# atmega2560_2.net
KiCad netlist of a schematic drawn in EAGLE
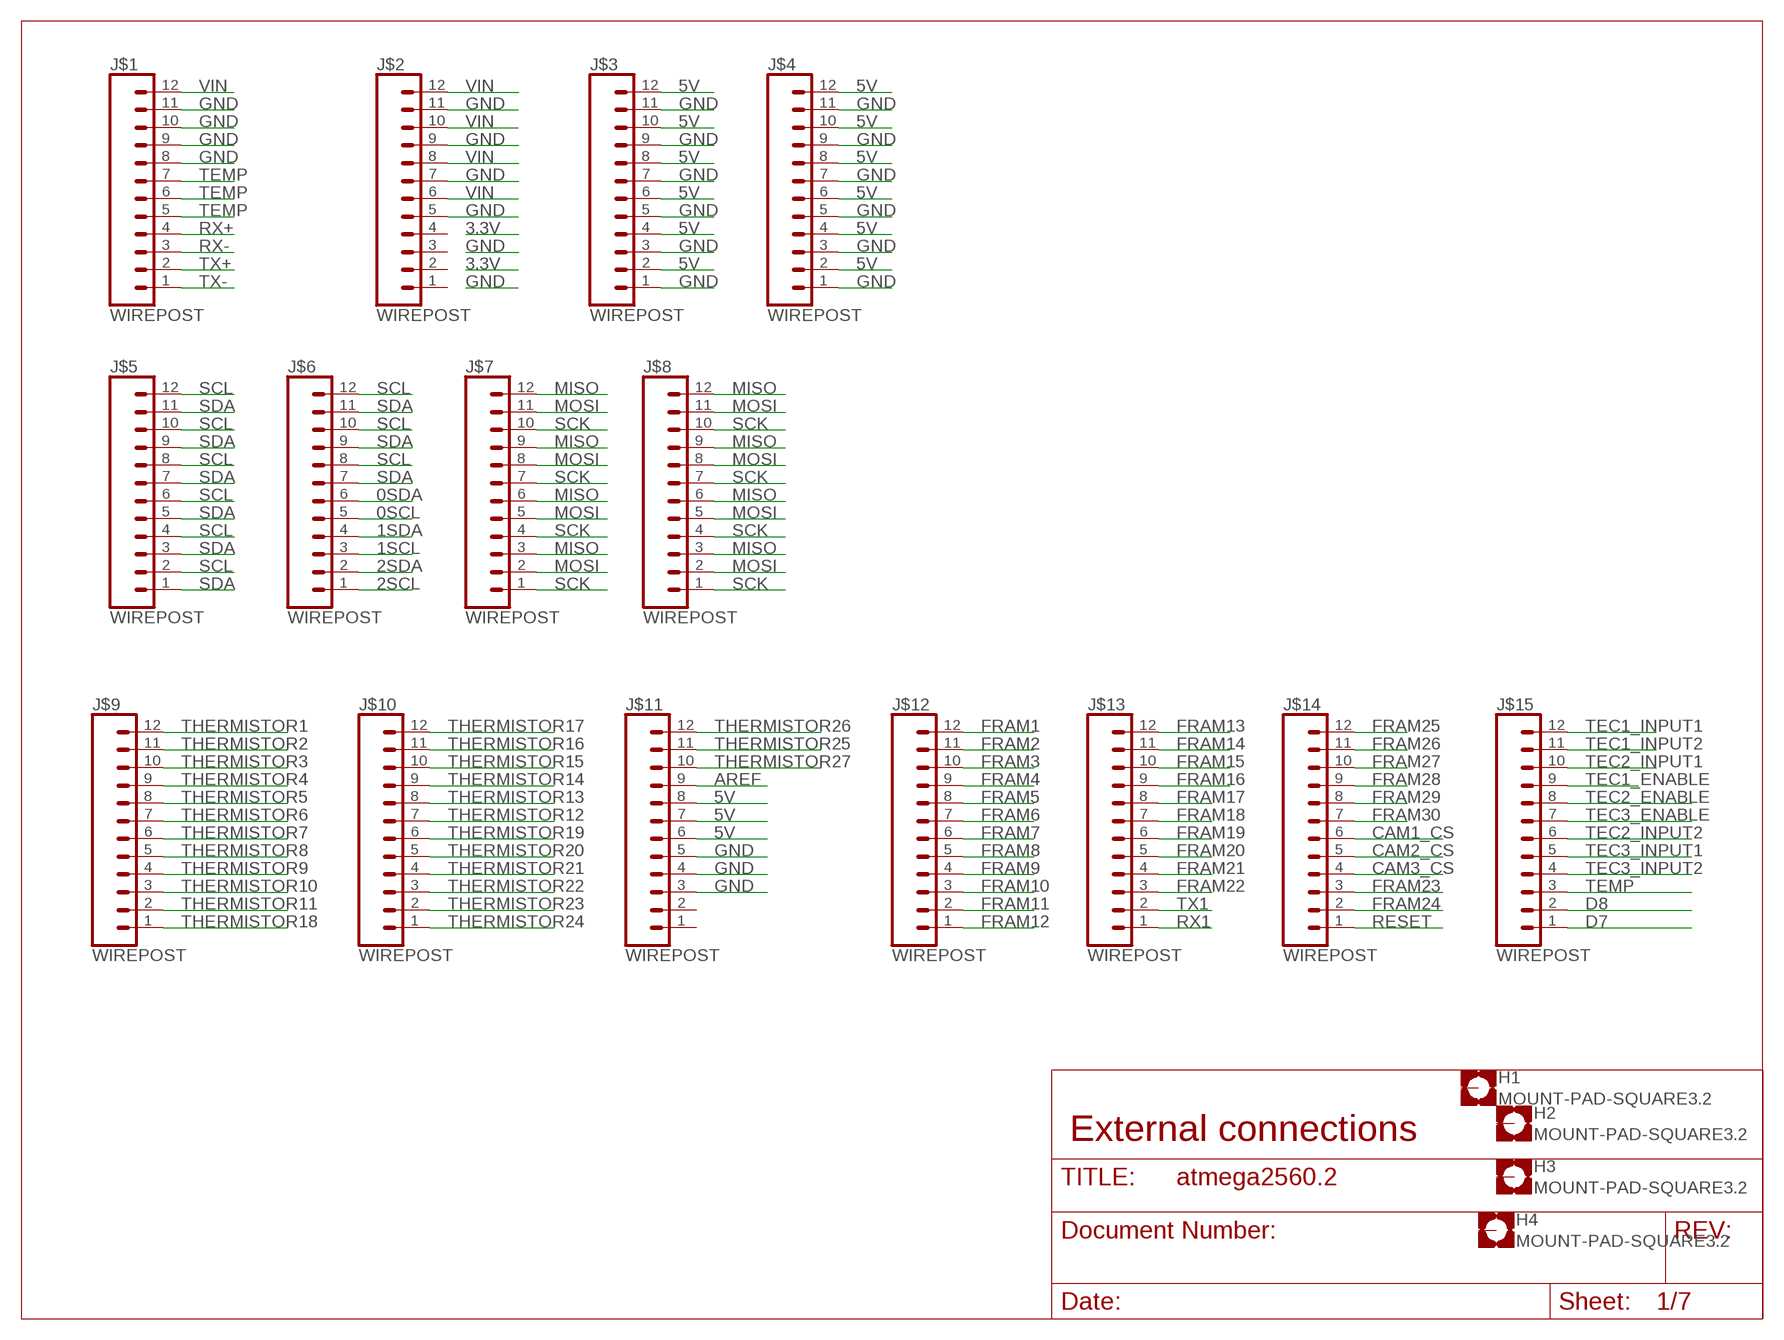
[diagram p0: schematic, sheet 1]
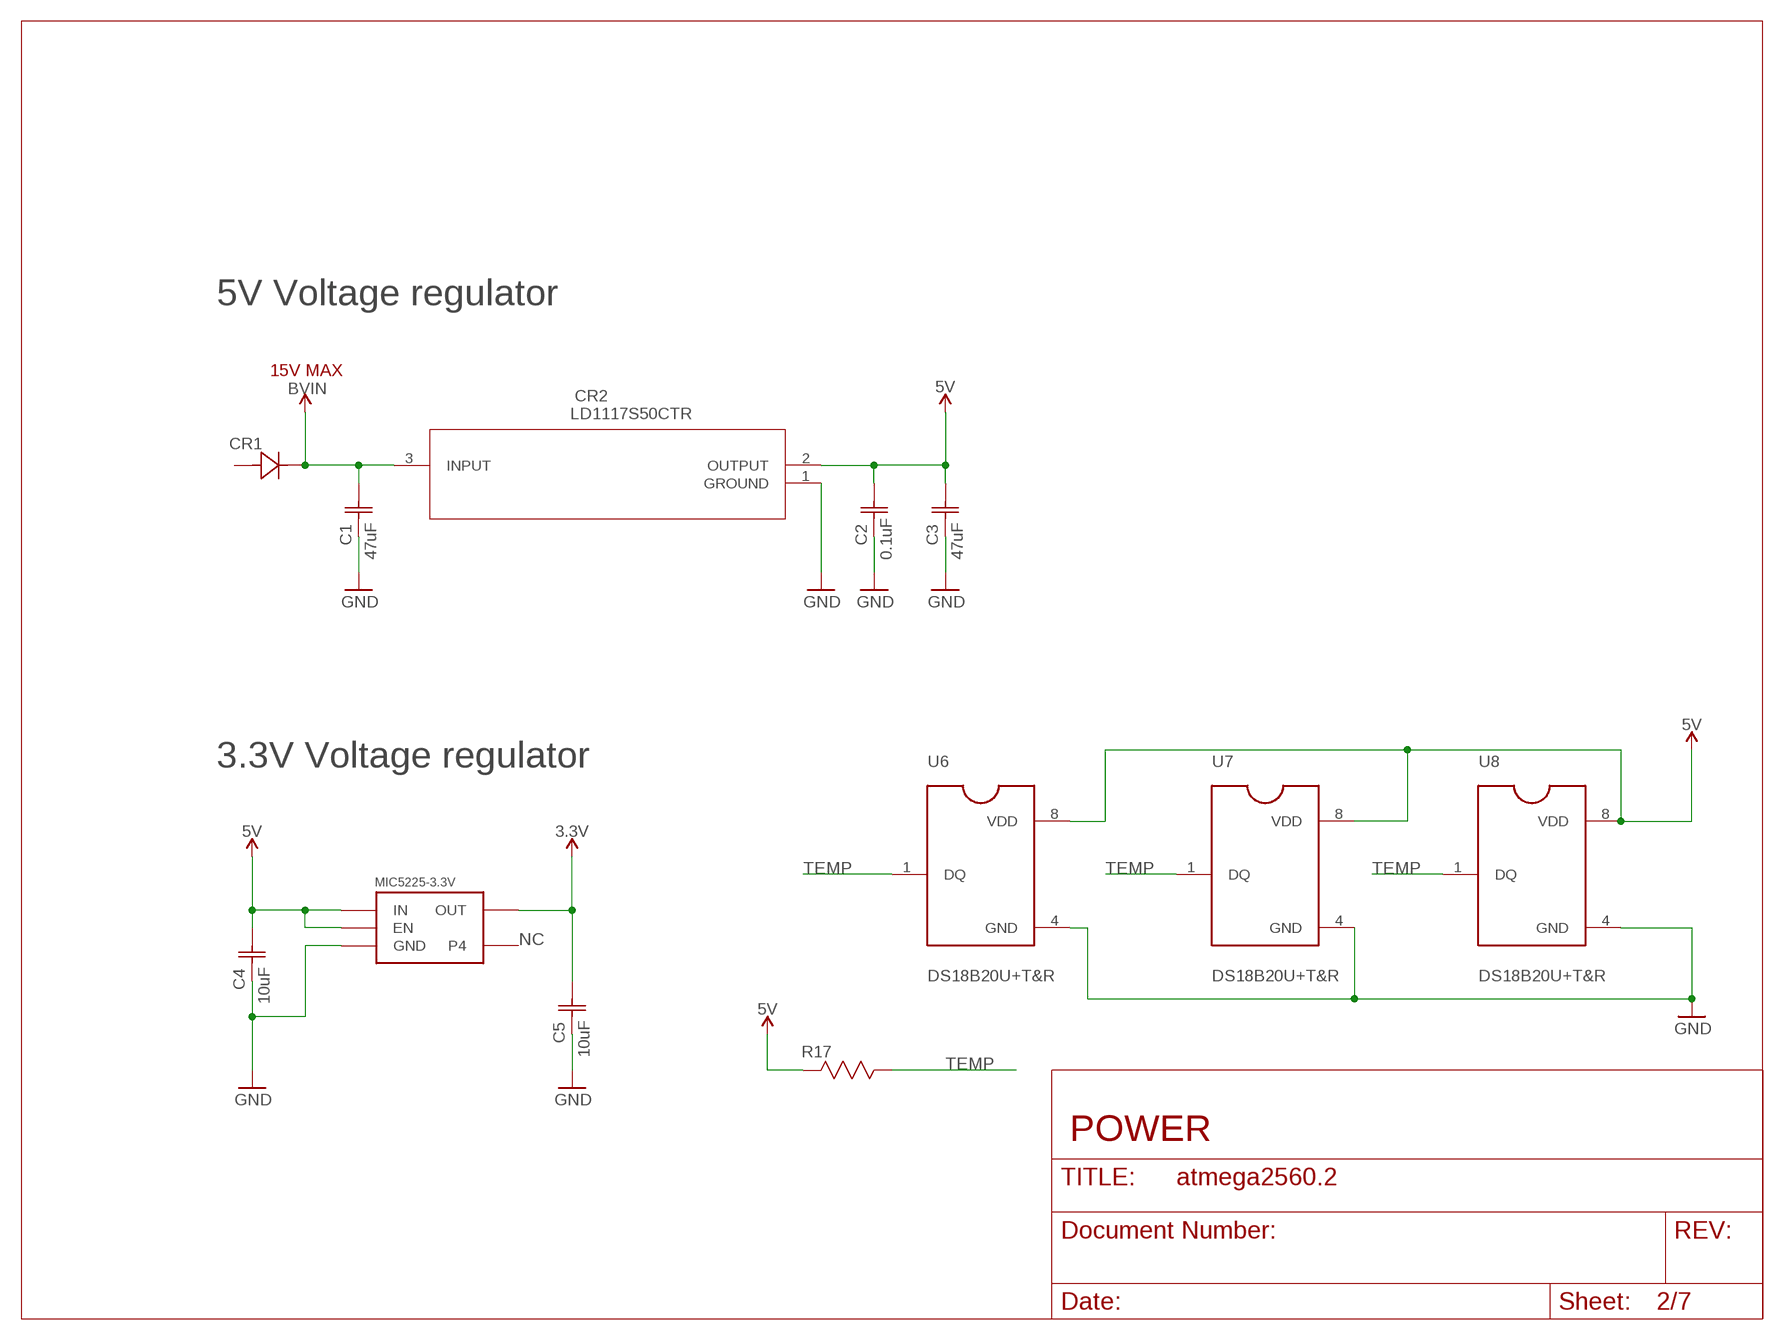
[diagram p1: schematic, sheet 2]
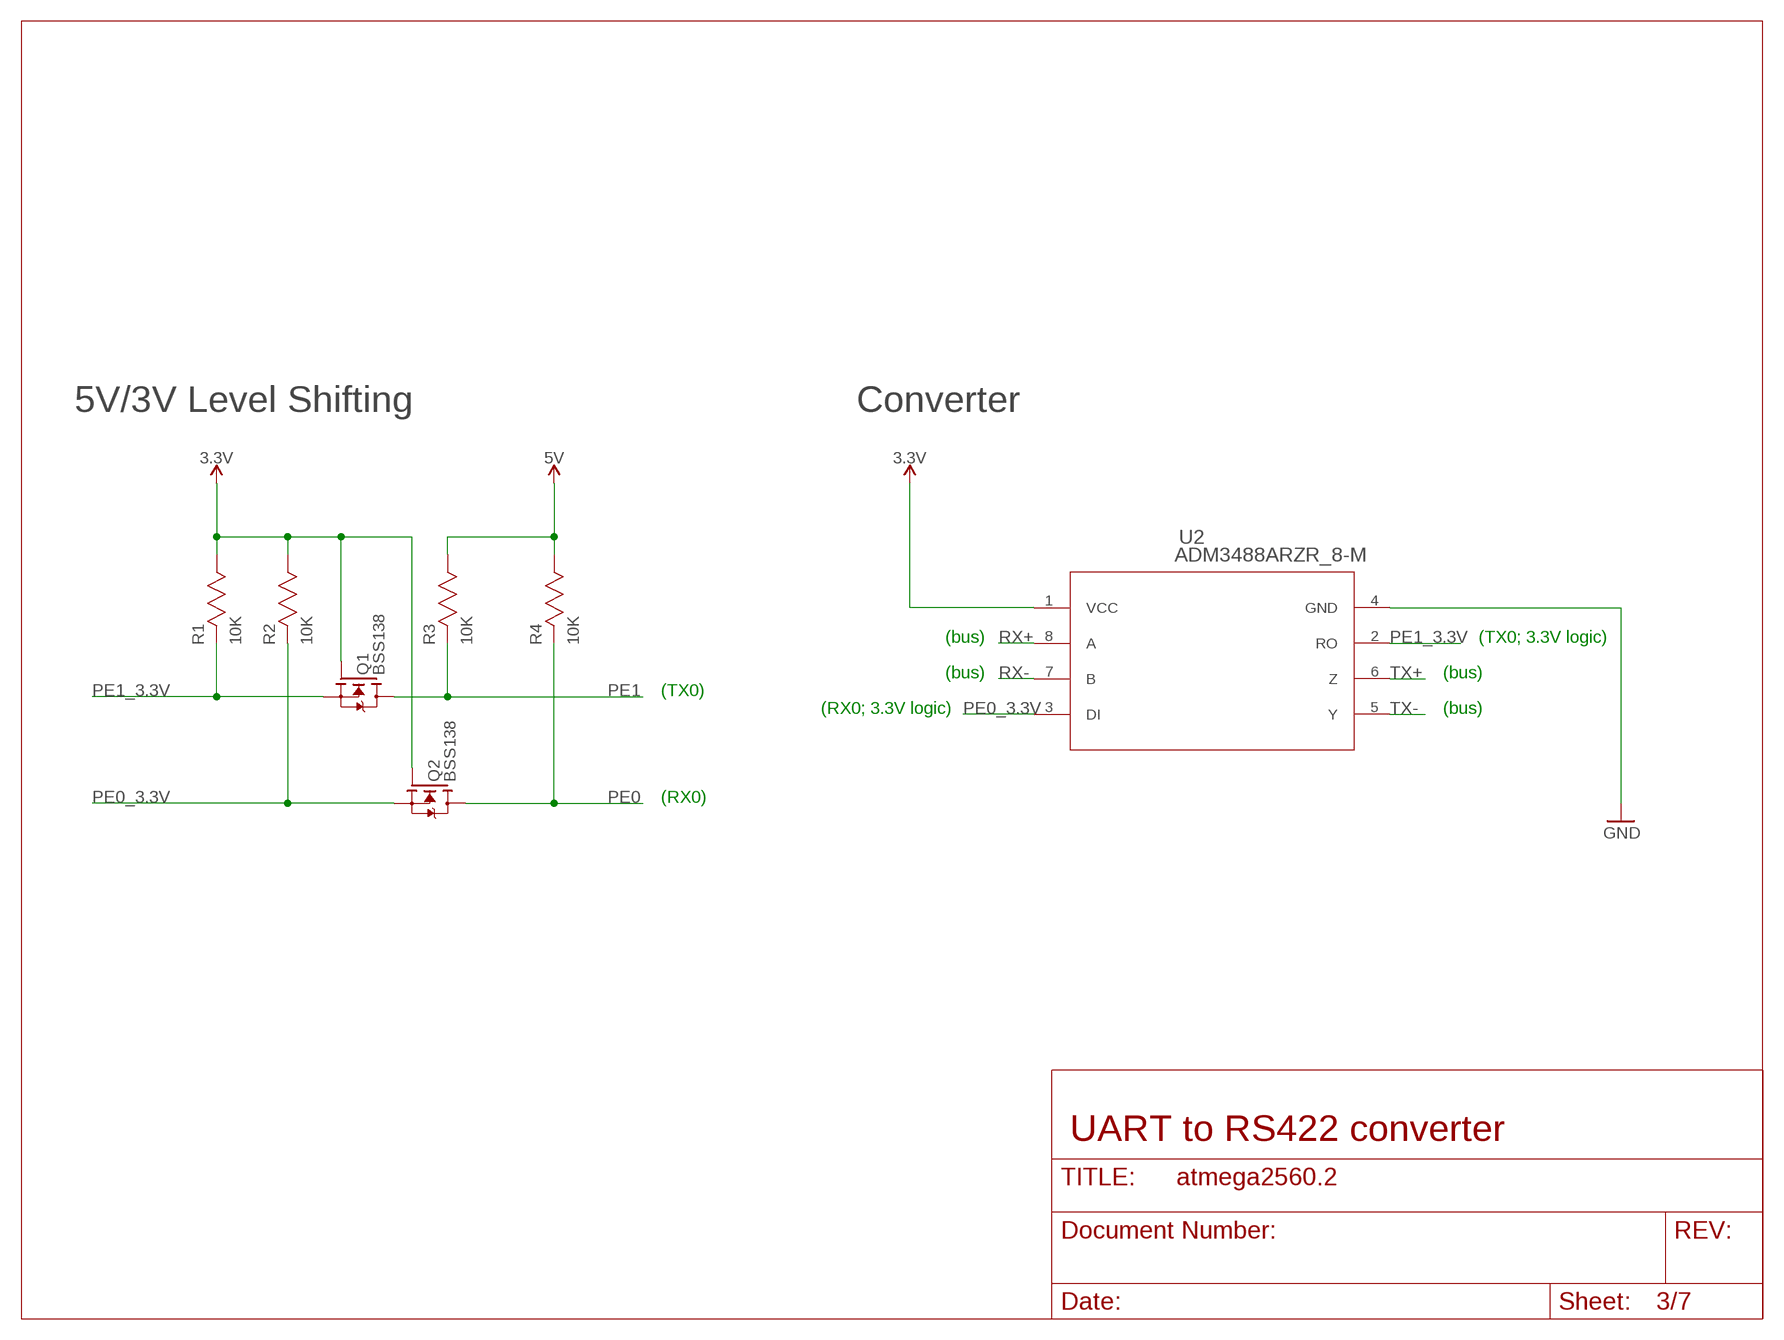
[diagram p2: schematic, sheet 3]
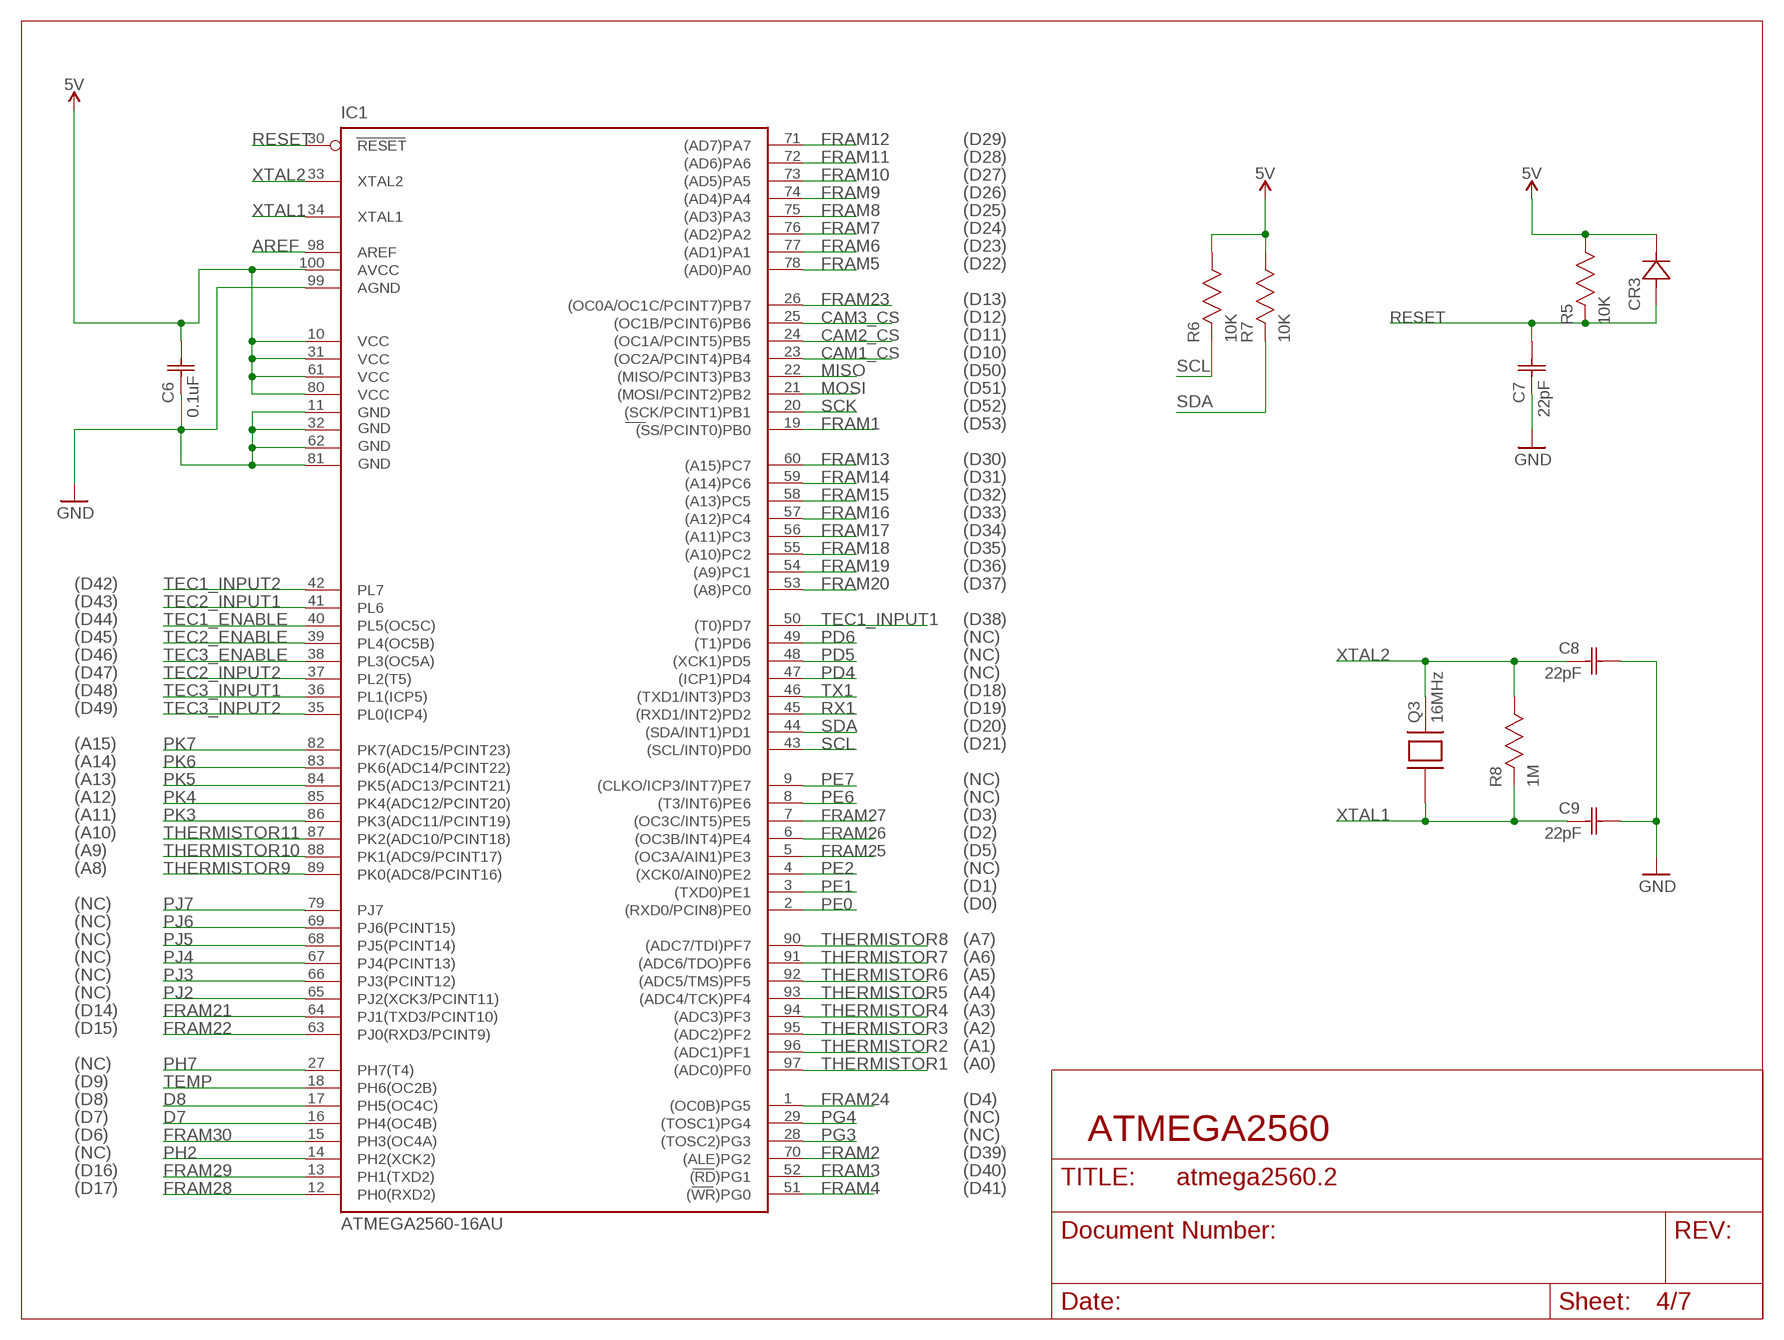
[diagram p3: schematic, sheet 4]
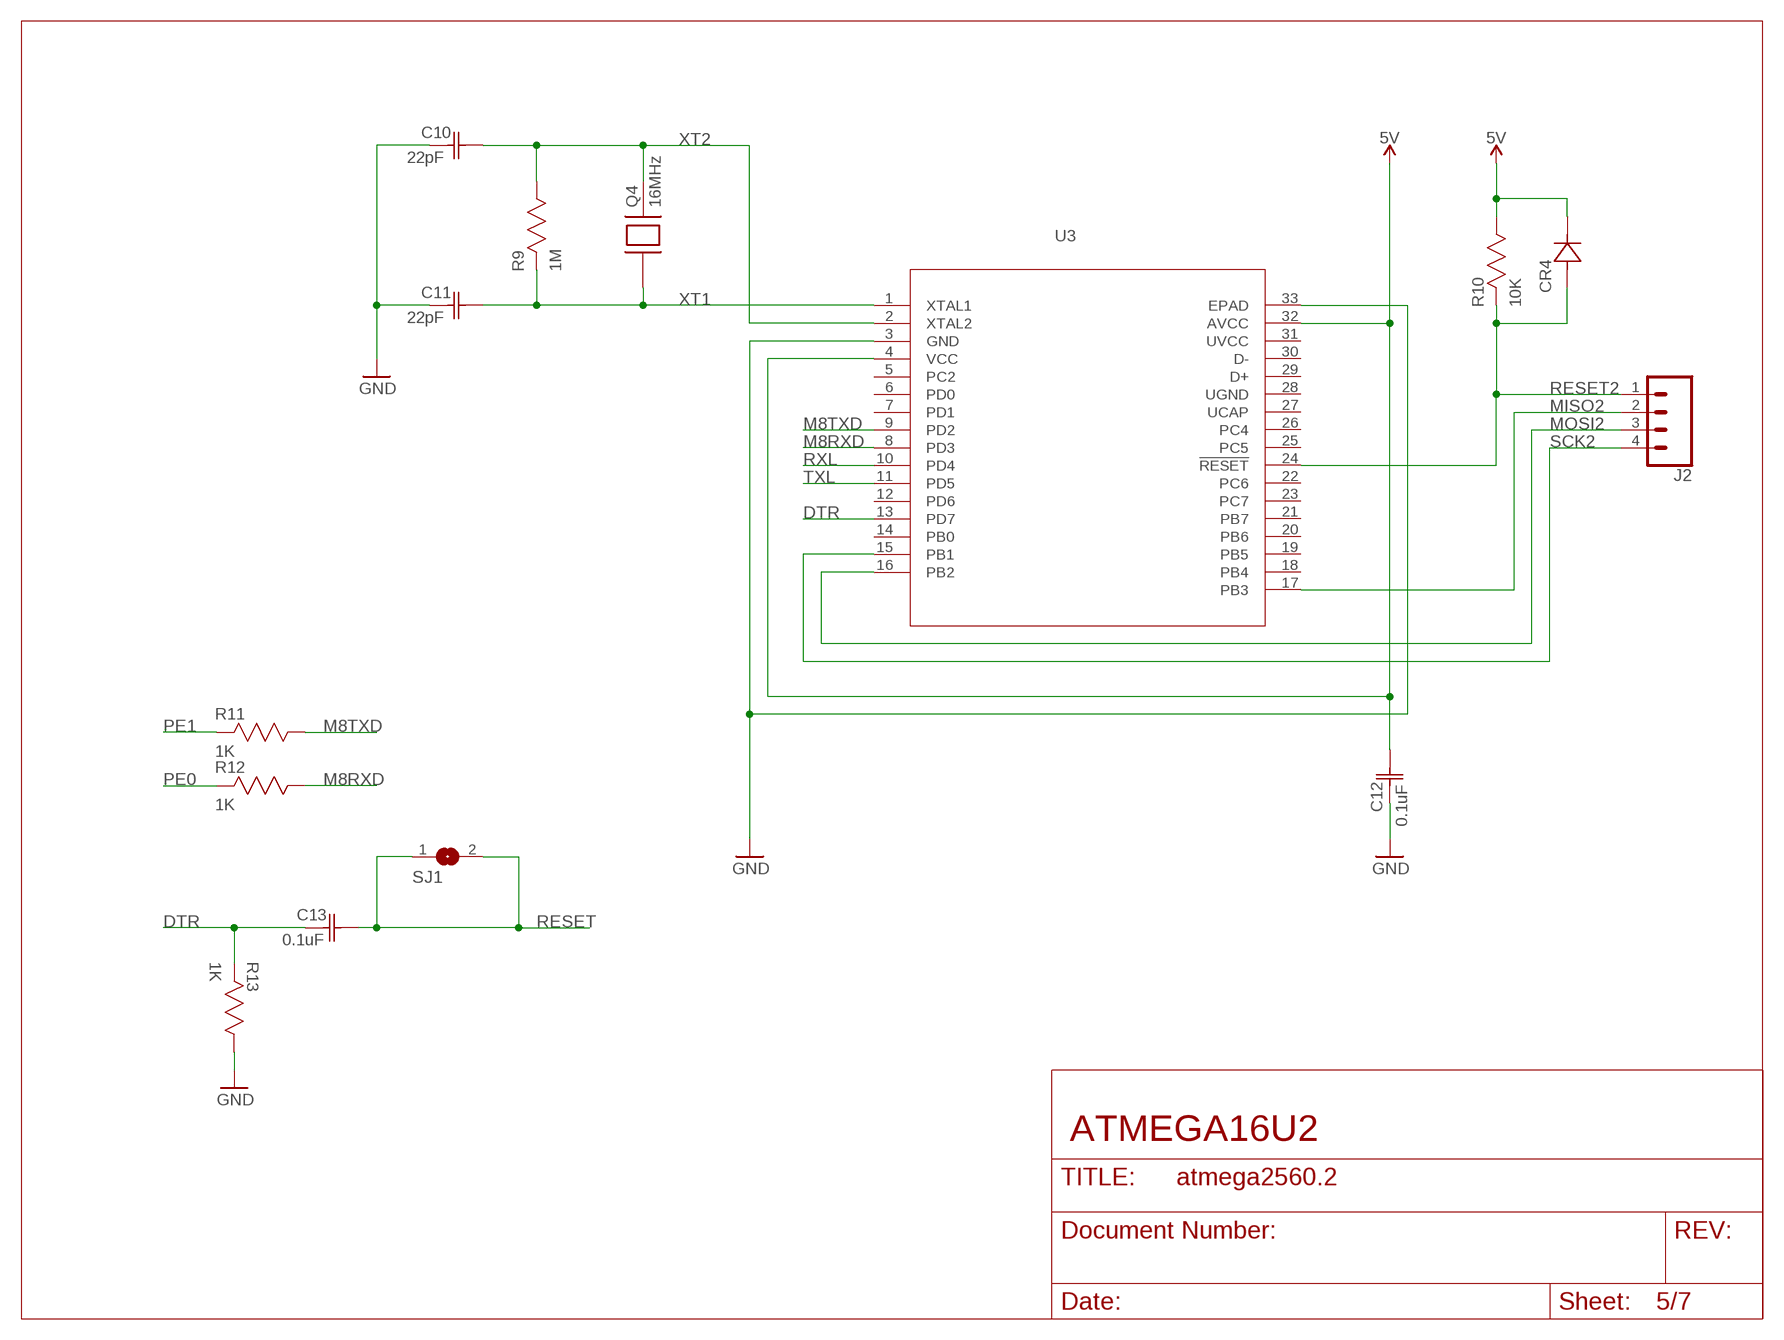
[diagram p4: schematic, sheet 5]
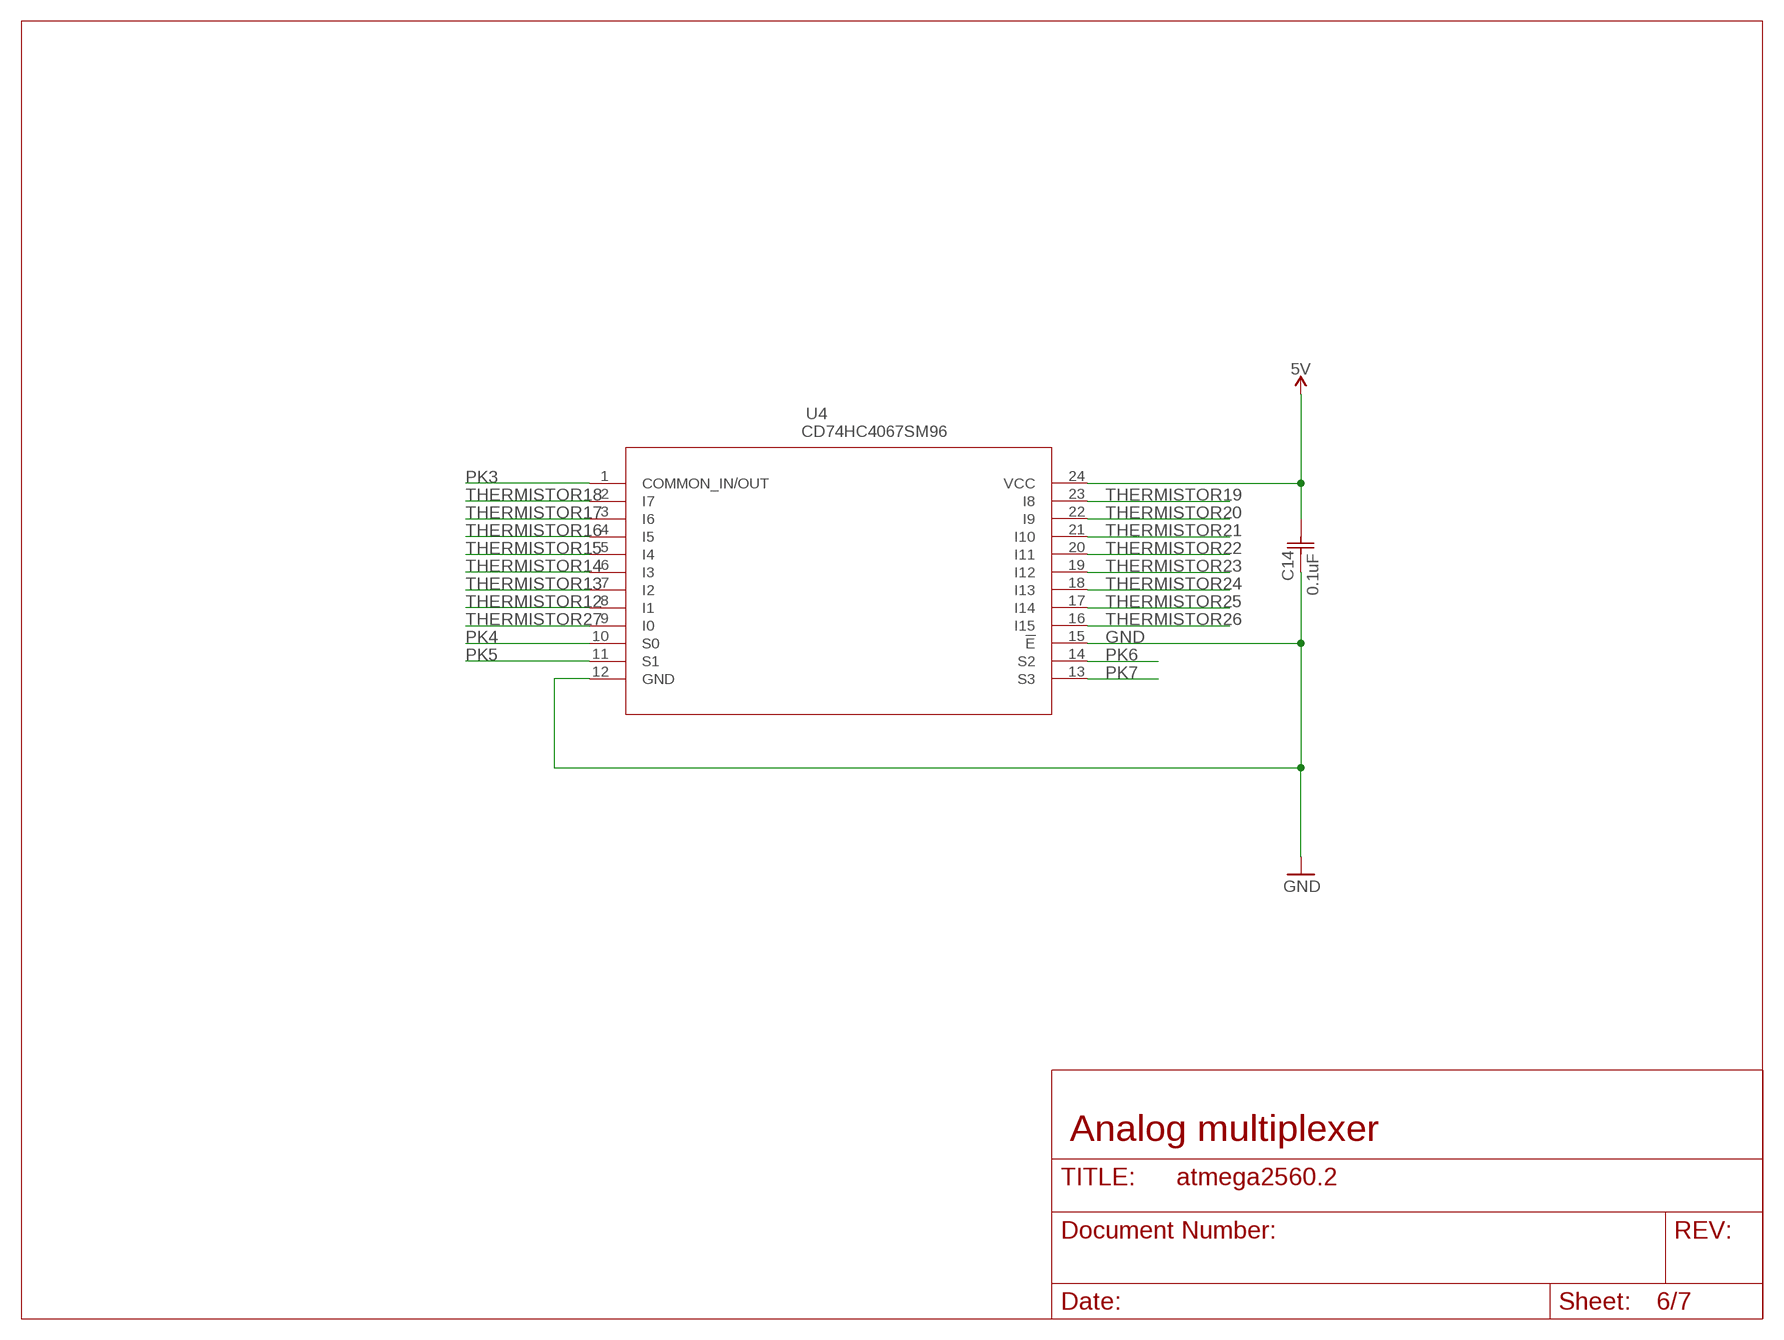
[diagram p5: schematic, sheet 6]
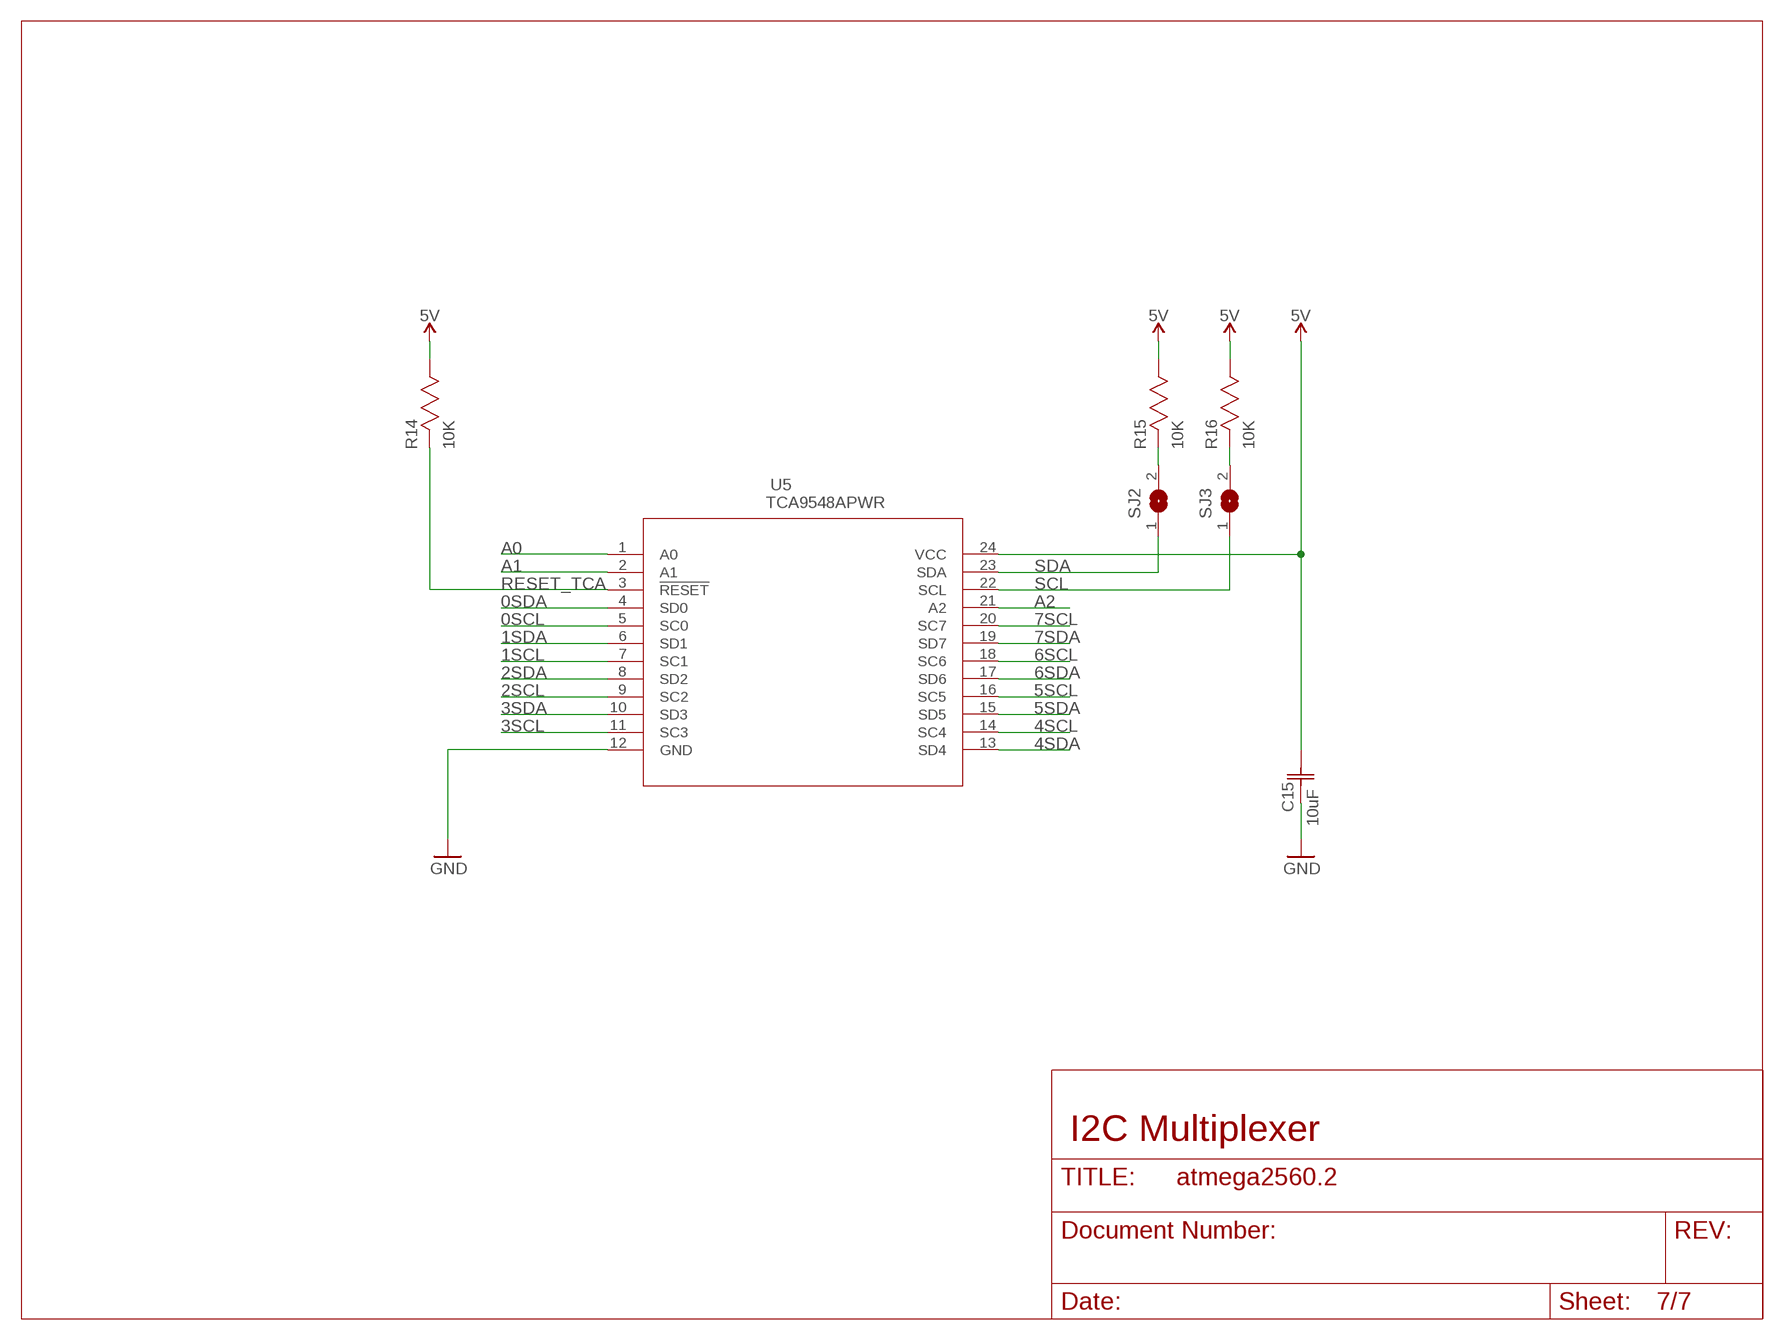
[diagram p6: schematic, sheet 7]

(export (version "E")
  (design (tool "Eeschema 10.0.6"))
  (components
    (comp (ref "C14")
      (value "0.1uF")
      (footprint "eagle-import:CAP_01")
      (fields (field (name "MANUFACTURER_PART_NUMBER") "CC0402KRX5R6BB104"))
      (libsource (lib "eagle-import") (part "CAP_01UF"))
    )
    (comp (ref "U4")
      (value "CD74HC4067SM96")
      (footprint "eagle-import:DB24")
      (libsource (lib "eagle-import") (part "CD74HC4067SM96"))
    )
    (comp (ref "Q1")
      (value "BSS138")
      (footprint "eagle-import:SOT-23")
      (fields (field (name "MANUFACTURER_PART_NUMBER") "BSS138TA"))
      (libsource (lib "eagle-import") (part "BSS138"))
    )
    (comp (ref "Q2")
      (value "BSS138")
      (footprint "eagle-import:SOT-23")
      (fields (field (name "MANUFACTURER_PART_NUMBER") "BSS138TA"))
      (libsource (lib "eagle-import") (part "BSS138"))
    )
    (comp (ref "R1")
      (value "10K")
      (footprint "eagle-import:RC0603N")
      (libsource (lib "eagle-import") (part "RES_10K"))
    )
    (comp (ref "R2")
      (value "10K")
      (footprint "eagle-import:RC0603N")
      (libsource (lib "eagle-import") (part "RES_10K"))
    )
    (comp (ref "R3")
      (value "10K")
      (footprint "eagle-import:RC0603N")
      (libsource (lib "eagle-import") (part "RES_10K"))
    )
    (comp (ref "R4")
      (value "10K")
      (footprint "eagle-import:RC0603N")
      (libsource (lib "eagle-import") (part "RES_10K"))
    )
    (comp (ref "U2")
      (value "ADM3488ARZR_8-M")
      (footprint "eagle-import:R_8-M")
      (fields (field (name "MANUFACTURER_PART_NUMBER") "ADM3488ARZ"))
      (libsource (lib "eagle-import") (part "ADM3488ARZR_8-M"))
    )
    (comp (ref "H1")
      (value "MOUNT-PAD-SQUARE3.2")
      (footprint "eagle-import:3,2-PAD-SQUARE")
      (libsource (lib "eagle-import") (part "MOUNT-PAD-SQUARE3.2"))
    )
    (comp (ref "H2")
      (value "MOUNT-PAD-SQUARE3.2")
      (footprint "eagle-import:3,2-PAD-SQUARE")
      (libsource (lib "eagle-import") (part "MOUNT-PAD-SQUARE3.2"))
    )
    (comp (ref "H3")
      (value "MOUNT-PAD-SQUARE3.2")
      (footprint "eagle-import:3,2-PAD-SQUARE")
      (libsource (lib "eagle-import") (part "MOUNT-PAD-SQUARE3.2"))
    )
    (comp (ref "H4")
      (value "MOUNT-PAD-SQUARE3.2")
      (footprint "eagle-import:3,2-PAD-SQUARE")
      (libsource (lib "eagle-import") (part "MOUNT-PAD-SQUARE3.2"))
    )
    (comp (ref "J$1")
      (value "WIREPOST")
      (footprint "eagle-import:WIREWRAPPOST")
      (libsource (lib "eagle-import") (part "WIREPOST"))
    )
    (comp (ref "J$2")
      (value "WIREPOST")
      (footprint "eagle-import:WIREWRAPPOST")
      (libsource (lib "eagle-import") (part "WIREPOST"))
    )
    (comp (ref "J$3")
      (value "WIREPOST")
      (footprint "eagle-import:WIREWRAPPOST")
      (libsource (lib "eagle-import") (part "WIREPOST"))
    )
    (comp (ref "J$4")
      (value "WIREPOST")
      (footprint "eagle-import:WIREWRAPPOST")
      (libsource (lib "eagle-import") (part "WIREPOST"))
    )
    (comp (ref "J$5")
      (value "WIREPOST")
      (footprint "eagle-import:WIREWRAPPOST")
      (libsource (lib "eagle-import") (part "WIREPOST"))
    )
    (comp (ref "J$6")
      (value "WIREPOST")
      (footprint "eagle-import:WIREWRAPPOST")
      (libsource (lib "eagle-import") (part "WIREPOST"))
    )
    (comp (ref "J$7")
      (value "WIREPOST")
      (footprint "eagle-import:WIREWRAPPOST")
      (libsource (lib "eagle-import") (part "WIREPOST"))
    )
    (comp (ref "J$8")
      (value "WIREPOST")
      (footprint "eagle-import:WIREWRAPPOST")
      (libsource (lib "eagle-import") (part "WIREPOST"))
    )
    (comp (ref "J$9")
      (value "WIREPOST")
      (footprint "eagle-import:WIREWRAPPOST")
      (libsource (lib "eagle-import") (part "WIREPOST"))
    )
    (comp (ref "J$10")
      (value "WIREPOST")
      (footprint "eagle-import:WIREWRAPPOST")
      (libsource (lib "eagle-import") (part "WIREPOST"))
    )
    (comp (ref "J$11")
      (value "WIREPOST")
      (footprint "eagle-import:WIREWRAPPOST")
      (libsource (lib "eagle-import") (part "WIREPOST"))
    )
    (comp (ref "J$12")
      (value "WIREPOST")
      (footprint "eagle-import:WIREWRAPPOST")
      (libsource (lib "eagle-import") (part "WIREPOST"))
    )
    (comp (ref "J$13")
      (value "WIREPOST")
      (footprint "eagle-import:WIREWRAPPOST")
      (libsource (lib "eagle-import") (part "WIREPOST"))
    )
    (comp (ref "J$14")
      (value "WIREPOST")
      (footprint "eagle-import:WIREWRAPPOST")
      (libsource (lib "eagle-import") (part "WIREPOST"))
    )
    (comp (ref "J$15")
      (value "WIREPOST")
      (footprint "eagle-import:WIREWRAPPOST")
      (libsource (lib "eagle-import") (part "WIREPOST"))
    )
    (comp (ref "C1")
      (value "47uF")
      (footprint "eagle-import:CAP_5750")
      (fields (field (name "MANUFACTURER_PART_NUMBER") "CGA9N3X7R1C476M230KB"))
      (libsource (lib "eagle-import") (part "CAP_47UF"))
    )
    (comp (ref "C2")
      (value "0.1uF")
      (footprint "eagle-import:CAP_01")
      (fields (field (name "MANUFACTURER_PART_NUMBER") "CC0402KRX5R6BB104"))
      (libsource (lib "eagle-import") (part "CAP_01UF"))
    )
    (comp (ref "C3")
      (value "47uF")
      (footprint "eagle-import:CAP_5750")
      (fields (field (name "MANUFACTURER_PART_NUMBER") "CGA9N3X7R1C476M230KB"))
      (libsource (lib "eagle-import") (part "CAP_47UF"))
    )
    (comp (ref "C4")
      (value "10uF")
      (footprint "eagle-import:CAP_GRM219R61A106KE44D")
      (libsource (lib "eagle-import") (part "CAP_10UF"))
    )
    (comp (ref "C5")
      (value "10uF")
      (footprint "eagle-import:CAP_GRM219R61A106KE44D")
      (libsource (lib "eagle-import") (part "CAP_10UF"))
    )
    (comp (ref "CR1")
      (value "DIODE_600V_3A")
      (footprint "eagle-import:DIODE_600V_3A")
      (fields (field (name "MANUFACTURER_PART_NUMBER") "RS3JB13F"))
      (libsource (lib "eagle-import") (part "DIODE_600V_3A"))
    )
    (comp (ref "CR2")
      (value "LD1117S50CTR")
      (footprint "eagle-import:SOT-223")
      (libsource (lib "eagle-import") (part "LD1117S50CTR"))
    )
    (comp (ref "R17")
      (value "RES_4_7K")
      (footprint "eagle-import:RC0603N")
      (libsource (lib "eagle-import") (part "RES_4_7K"))
    )
    (comp (ref "U1")
      (value "MIC5225")
      (footprint "eagle-import:SOT23-5")
      (libsource (lib "eagle-import") (part "MIC5225"))
    )
    (comp (ref "U6")
      (value "DS18B20U+T&R")
      (footprint "eagle-import:SOP65P500X110-8N")
      (fields (field (name "MF") "Maxim Integrated") (field (name "MP") "DS18B20U+T&amp;R"))
      (libsource (lib "eagle-import") (part "DS18B20U+T&R"))
    )
    (comp (ref "U7")
      (value "DS18B20U+T&R")
      (footprint "eagle-import:SOP65P500X110-8N")
      (fields (field (name "MF") "Maxim Integrated") (field (name "MP") "DS18B20U+T&amp;R"))
      (libsource (lib "eagle-import") (part "DS18B20U+T&R"))
    )
    (comp (ref "U8")
      (value "DS18B20U+T&R")
      (footprint "eagle-import:SOP65P500X110-8N")
      (fields (field (name "MF") "Maxim Integrated") (field (name "MP") "DS18B20U+T&amp;R"))
      (libsource (lib "eagle-import") (part "DS18B20U+T&R"))
    )
    (comp (ref "C15")
      (value "10uF")
      (footprint "eagle-import:CAP_GRM219R61A106KE44D")
      (libsource (lib "eagle-import") (part "CAP_10UF"))
    )
    (comp (ref "R14")
      (value "10K")
      (footprint "eagle-import:RC0603N")
      (libsource (lib "eagle-import") (part "RES_10K"))
    )
    (comp (ref "R15")
      (value "10K")
      (footprint "eagle-import:RC0603N")
      (libsource (lib "eagle-import") (part "RES_10K"))
    )
    (comp (ref "R16")
      (value "10K")
      (footprint "eagle-import:RC0603N")
      (libsource (lib "eagle-import") (part "RES_10K"))
    )
    (comp (ref "SJ2")
      (value "SOLDERJUMPERCLOSED")
      (footprint "eagle-import:SOLDERJUMPER_CLOSEDWIRE")
      (libsource (lib "eagle-import") (part "SOLDERJUMPERCLOSED"))
    )
    (comp (ref "SJ3")
      (value "SOLDERJUMPERCLOSED")
      (footprint "eagle-import:SOLDERJUMPER_CLOSEDWIRE")
      (libsource (lib "eagle-import") (part "SOLDERJUMPERCLOSED"))
    )
    (comp (ref "U5")
      (value "TCA9548APWR")
      (footprint "eagle-import:PW24")
      (libsource (lib "eagle-import") (part "TCA9548APWR"))
    )
    (comp (ref "C10")
      (value "22pF")
      (footprint "eagle-import:CC0805N")
      (libsource (lib "eagle-import") (part "CAP_22PF"))
    )
    (comp (ref "C11")
      (value "22pF")
      (footprint "eagle-import:CC0805N")
      (libsource (lib "eagle-import") (part "CAP_22PF"))
    )
    (comp (ref "C12")
      (value "0.1uF")
      (footprint "eagle-import:CAP_01")
      (fields (field (name "MANUFACTURER_PART_NUMBER") "CC0402KRX5R6BB104"))
      (libsource (lib "eagle-import") (part "CAP_01UF"))
    )
    (comp (ref "C13")
      (value "0.1uF")
      (footprint "eagle-import:CAP_01")
      (fields (field (name "MANUFACTURER_PART_NUMBER") "CC0402KRX5R6BB104"))
      (libsource (lib "eagle-import") (part "CAP_01UF"))
    )
    (comp (ref "CR4")
      (value "DIODE_600V_3A")
      (footprint "eagle-import:DIODE_600V_3A")
      (fields (field (name "MANUFACTURER_PART_NUMBER") "RS3JB13F"))
      (libsource (lib "eagle-import") (part "DIODE_600V_3A"))
    )
    (comp (ref "J2")
      (value "CONN_04")
      (footprint "eagle-import:1X04")
      (libsource (lib "eagle-import") (part "CONN_04"))
    )
    (comp (ref "Q4")
      (value "16MHz")
      (footprint "eagle-import:OSCILLATOR")
      (libsource (lib "eagle-import") (part "OSILLATOR"))
    )
    (comp (ref "R9")
      (value "1M")
      (footprint "eagle-import:RC0603N")
      (libsource (lib "eagle-import") (part "RES_1M"))
    )
    (comp (ref "R10")
      (value "10K")
      (footprint "eagle-import:RC0603N")
      (libsource (lib "eagle-import") (part "RES_10K"))
    )
    (comp (ref "R11")
      (value "1K")
      (footprint "eagle-import:RC0603N")
      (libsource (lib "eagle-import") (part "RES_1K"))
    )
    (comp (ref "R12")
      (value "1K")
      (footprint "eagle-import:RC0603N")
      (libsource (lib "eagle-import") (part "RES_1K"))
    )
    (comp (ref "R13")
      (value "1K")
      (footprint "eagle-import:RC0603N")
      (libsource (lib "eagle-import") (part "RES_1K"))
    )
    (comp (ref "SJ1") (value "SJ") (footprint "eagle-import:SJ") (libsource (lib "eagle-import") (part "SJ")))
    (comp (ref "U3")
      (value "ATMEGA16U2-MU")
      (footprint "eagle-import:32M1-A")
      (fields (field (name "MANUFACTURER_PART_NUMBER") "ATMEGA16U2MU"))
      (libsource (lib "eagle-import") (part "ATMEGA16U2-MU"))
    )
    (comp (ref "C6")
      (value "0.1uF")
      (footprint "eagle-import:CAP_01")
      (fields (field (name "MANUFACTURER_PART_NUMBER") "CC0402KRX5R6BB104"))
      (libsource (lib "eagle-import") (part "CAP_01UF"))
    )
    (comp (ref "C7")
      (value "22pF")
      (footprint "eagle-import:CC0805N")
      (libsource (lib "eagle-import") (part "CAP_22PF"))
    )
    (comp (ref "C8")
      (value "22pF")
      (footprint "eagle-import:CC0805N")
      (libsource (lib "eagle-import") (part "CAP_22PF"))
    )
    (comp (ref "C9")
      (value "22pF")
      (footprint "eagle-import:CC0805N")
      (libsource (lib "eagle-import") (part "CAP_22PF"))
    )
    (comp (ref "CR3")
      (value "DIODE_600V_3A")
      (footprint "eagle-import:DIODE_600V_3A")
      (fields (field (name "MANUFACTURER_PART_NUMBER") "RS3JB13F"))
      (libsource (lib "eagle-import") (part "DIODE_600V_3A"))
    )
    (comp (ref "IC1")
      (value "ATMEGA2560-16AU")
      (footprint "eagle-import:TQFP100")
      (libsource (lib "eagle-import") (part "ATMEGA2560AU2560-16"))
    )
    (comp (ref "Q3")
      (value "16MHz")
      (footprint "eagle-import:OSCILLATOR")
      (libsource (lib "eagle-import") (part "OSILLATOR"))
    )
    (comp (ref "R5")
      (value "10K")
      (footprint "eagle-import:RC0603N")
      (libsource (lib "eagle-import") (part "RES_10K"))
    )
    (comp (ref "R6")
      (value "10K")
      (footprint "eagle-import:RC0603N")
      (libsource (lib "eagle-import") (part "RES_10K"))
    )
    (comp (ref "R7")
      (value "10K")
      (footprint "eagle-import:RC0603N")
      (libsource (lib "eagle-import") (part "RES_10K"))
    )
    (comp (ref "R8")
      (value "1M")
      (footprint "eagle-import:RC0603N")
      (libsource (lib "eagle-import") (part "RES_1M"))
    )
  )
  (nets
    (net (code "1") (name "0SCL") (class "Default")
      (node (ref "J$6") (pin "5") (pinfunction "5_5") (pintype "passive"))
      (node (ref "U5") (pin "5") (pinfunction "SC0_5") (pintype "passive"))
    )
    (net (code "2") (name "0SDA") (class "Default")
      (node (ref "J$6") (pin "6") (pinfunction "6_6") (pintype "passive"))
      (node (ref "U5") (pin "4") (pinfunction "SD0_4") (pintype "passive"))
    )
    (net (code "3") (name "1SCL") (class "Default")
      (node (ref "J$6") (pin "3") (pinfunction "3_3") (pintype "passive"))
      (node (ref "U5") (pin "7") (pinfunction "SC1_7") (pintype "passive"))
    )
    (net (code "4") (name "1SDA") (class "Default")
      (node (ref "J$6") (pin "4") (pinfunction "4_4") (pintype "passive"))
      (node (ref "U5") (pin "6") (pinfunction "SD1_6") (pintype "passive"))
    )
    (net (code "5") (name "2SCL") (class "Default")
      (node (ref "J$6") (pin "1") (pinfunction "1_1") (pintype "passive"))
      (node (ref "U5") (pin "9") (pinfunction "SC2_9") (pintype "passive"))
    )
    (net (code "6") (name "2SDA") (class "Default")
      (node (ref "J$6") (pin "2") (pinfunction "2_2") (pintype "passive"))
      (node (ref "U5") (pin "8") (pinfunction "SD2_8") (pintype "passive"))
    )
    (net (code "7") (name "3.3V") (class "Default")
      (node (ref "C5") (pin "2") (pinfunction "2_2") (pintype "passive"))
      (node (ref "Q1") (pin "G") (pinfunction "G_G") (pintype "passive"))
      (node (ref "Q2") (pin "G") (pinfunction "G_G") (pintype "passive"))
      (node (ref "R1") (pin "1") (pinfunction "11_1") (pintype "passive"))
      (node (ref "R2") (pin "1") (pinfunction "11_1") (pintype "passive"))
      (node (ref "U1") (pin "OUT") (pinfunction "OUT_OUT") (pintype "bidirectional"))
      (node (ref "U2") (pin "1") (pinfunction "VCC_1") (pintype "passive"))
    )
    (net (code "8") (name "3SCL") (class "Default")
      (node (ref "U5") (pin "11") (pinfunction "SC3_11") (pintype "passive"))
    )
    (net (code "9") (name "3SDA") (class "Default")
      (node (ref "U5") (pin "10") (pinfunction "SD3_10") (pintype "passive"))
    )
    (net (code "10") (name "4SCL") (class "Default")
      (node (ref "U5") (pin "14") (pinfunction "SC4_14") (pintype "passive"))
    )
    (net (code "11") (name "4SDA") (class "Default")
      (node (ref "U5") (pin "13") (pinfunction "SD4_13") (pintype "passive"))
    )
    (net (code "12") (name "5SCL") (class "Default")
      (node (ref "U5") (pin "16") (pinfunction "SC5_16") (pintype "passive"))
    )
    (net (code "13") (name "5SDA") (class "Default")
      (node (ref "U5") (pin "15") (pinfunction "SD5_15") (pintype "passive"))
    )
    (net (code "14") (name "5V") (class "Default")
      (node (ref "C12") (pin "2") (pinfunction "2_2") (pintype "passive"))
      (node (ref "C14") (pin "2") (pinfunction "2_2") (pintype "passive"))
      (node (ref "C15") (pin "2") (pinfunction "2_2") (pintype "passive"))
      (node (ref "C2") (pin "2") (pinfunction "2_2") (pintype "passive"))
      (node (ref "C3") (pin "2") (pinfunction "2_2") (pintype "passive"))
      (node (ref "C4") (pin "2") (pinfunction "2_2") (pintype "passive"))
      (node (ref "C6") (pin "2") (pinfunction "2_2") (pintype "passive"))
      (node (ref "CR2") (pin "2") (pinfunction "OUTPUT_2") (pintype "passive"))
      (node (ref "CR3") (pin "1") (pinfunction "12_1") (pintype "passive"))
      (node (ref "CR4") (pin "1") (pinfunction "12_1") (pintype "passive"))
      (node (ref "IC1") (pin "10") (pinfunction "VCC_10") (pintype "power_in"))
      (node (ref "IC1") (pin "100") (pinfunction "AVCC_100") (pintype "power_in"))
      (node (ref "IC1") (pin "31") (pinfunction "VCC1_31") (pintype "power_in"))
      (node (ref "IC1") (pin "61") (pinfunction "VCC2_61") (pintype "power_in"))
      (node (ref "IC1") (pin "80") (pinfunction "VCC3_80") (pintype "power_in"))
      (node (ref "J$11") (pin "6") (pinfunction "6_6") (pintype "passive"))
      (node (ref "J$11") (pin "7") (pinfunction "7_7") (pintype "passive"))
      (node (ref "J$11") (pin "8") (pinfunction "8_8") (pintype "passive"))
      (node (ref "J$3") (pin "10") (pinfunction "10_10") (pintype "passive"))
      (node (ref "J$3") (pin "12") (pinfunction "12_12") (pintype "passive"))
      (node (ref "J$3") (pin "2") (pinfunction "2_2") (pintype "passive"))
      (node (ref "J$3") (pin "4") (pinfunction "4_4") (pintype "passive"))
      (node (ref "J$3") (pin "6") (pinfunction "6_6") (pintype "passive"))
      (node (ref "J$3") (pin "8") (pinfunction "8_8") (pintype "passive"))
      (node (ref "J$4") (pin "10") (pinfunction "10_10") (pintype "passive"))
      (node (ref "J$4") (pin "12") (pinfunction "12_12") (pintype "passive"))
      (node (ref "J$4") (pin "2") (pinfunction "2_2") (pintype "passive"))
      (node (ref "J$4") (pin "4") (pinfunction "4_4") (pintype "passive"))
      (node (ref "J$4") (pin "6") (pinfunction "6_6") (pintype "passive"))
      (node (ref "J$4") (pin "8") (pinfunction "8_8") (pintype "passive"))
      (node (ref "R10") (pin "1") (pinfunction "11_1") (pintype "passive"))
      (node (ref "R14") (pin "1") (pinfunction "11_1") (pintype "passive"))
      (node (ref "R15") (pin "1") (pinfunction "11_1") (pintype "passive"))
      (node (ref "R16") (pin "1") (pinfunction "11_1") (pintype "passive"))
      (node (ref "R17") (pin "2") (pinfunction "22_2") (pintype "passive"))
      (node (ref "R3") (pin "1") (pinfunction "11_1") (pintype "passive"))
      (node (ref "R4") (pin "1") (pinfunction "11_1") (pintype "passive"))
      (node (ref "R5") (pin "1") (pinfunction "11_1") (pintype "passive"))
      (node (ref "R6") (pin "1") (pinfunction "11_1") (pintype "passive"))
      (node (ref "R7") (pin "1") (pinfunction "11_1") (pintype "passive"))
      (node (ref "U1") (pin "EN") (pinfunction "EN_EN") (pintype "bidirectional"))
      (node (ref "U1") (pin "IN") (pinfunction "IN_IN") (pintype "bidirectional"))
      (node (ref "U3") (pin "32") (pinfunction "AVCC_32") (pintype "power_in"))
      (node (ref "U3") (pin "4") (pinfunction "VCC_4") (pintype "power_in"))
      (node (ref "U4") (pin "24") (pinfunction "VCC_24") (pintype "power_in"))
      (node (ref "U5") (pin "24") (pinfunction "VCC_24") (pintype "power_in"))
      (node (ref "U6") (pin "8") (pinfunction "VDD_8") (pintype "power_in"))
      (node (ref "U7") (pin "8") (pinfunction "VDD_8") (pintype "power_in"))
      (node (ref "U8") (pin "8") (pinfunction "VDD_8") (pintype "power_in"))
    )
    (net (code "15") (name "6SCL") (class "Default")
      (node (ref "U5") (pin "18") (pinfunction "SC6_18") (pintype "passive"))
    )
    (net (code "16") (name "6SDA") (class "Default")
      (node (ref "U5") (pin "17") (pinfunction "SD6_17") (pintype "passive"))
    )
    (net (code "17") (name "7SCL") (class "Default")
      (node (ref "U5") (pin "20") (pinfunction "SC7_20") (pintype "passive"))
    )
    (net (code "18") (name "7SDA") (class "Default")
      (node (ref "U5") (pin "19") (pinfunction "SD7_19") (pintype "passive"))
    )
    (net (code "19") (name "A0") (class "Default")
      (node (ref "U5") (pin "1") (pinfunction "A0_1") (pintype "input"))
    )
    (net (code "20") (name "A1") (class "Default")
      (node (ref "U5") (pin "2") (pinfunction "A1_2") (pintype "input"))
    )
    (net (code "21") (name "A2") (class "Default")
      (node (ref "U5") (pin "21") (pinfunction "A2_21") (pintype "input"))
    )
    (net (code "22") (name "AREF") (class "Default")
      (node (ref "IC1") (pin "98") (pinfunction "AREF_98") (pintype "bidirectional"))
      (node (ref "J$11") (pin "9") (pinfunction "9_9") (pintype "passive"))
    )
    (net (code "23") (name "CAM1_CS") (class "Default")
      (node (ref "IC1") (pin "23") (pinfunction "(OC2A/PCINT4)PB4_23") (pintype "bidirectional"))
      (node (ref "J$14") (pin "6") (pinfunction "6_6") (pintype "passive"))
    )
    (net (code "24") (name "CAM2_CS") (class "Default")
      (node (ref "IC1") (pin "24") (pinfunction "(OC1A/PCINT5)PB5_24") (pintype "bidirectional"))
      (node (ref "J$14") (pin "5") (pinfunction "5_5") (pintype "passive"))
    )
    (net (code "25") (name "CAM3_CS") (class "Default")
      (node (ref "IC1") (pin "25") (pinfunction "(OC1B/PCINT6)PB6_25") (pintype "bidirectional"))
      (node (ref "J$14") (pin "4") (pinfunction "4_4") (pintype "passive"))
    )
    (net (code "26") (name "D7") (class "Default")
      (node (ref "IC1") (pin "16") (pinfunction "PH4(OC4B)_16") (pintype "bidirectional"))
      (node (ref "J$15") (pin "1") (pinfunction "1_1") (pintype "passive"))
    )
    (net (code "27") (name "D8") (class "Default")
      (node (ref "IC1") (pin "17") (pinfunction "PH5(OC4C)_17") (pintype "bidirectional"))
      (node (ref "J$15") (pin "2") (pinfunction "2_2") (pintype "passive"))
    )
    (net (code "28") (name "DTR") (class "Default")
      (node (ref "C13") (pin "1") (pinfunction "1_1") (pintype "passive"))
      (node (ref "R13") (pin "2") (pinfunction "22_2") (pintype "passive"))
      (node (ref "U3") (pin "13") (pinfunction "PD7_13") (pintype "bidirectional"))
    )
    (net (code "29") (name "FRAM1") (class "Default")
      (node (ref "IC1") (pin "19") (pinfunction "(SS/PCINT0)PB0_19") (pintype "bidirectional"))
      (node (ref "J$12") (pin "12") (pinfunction "12_12") (pintype "passive"))
    )
    (net (code "30") (name "FRAM2") (class "Default")
      (node (ref "IC1") (pin "70") (pinfunction "(ALE)PG2_70") (pintype "bidirectional"))
      (node (ref "J$12") (pin "11") (pinfunction "11_11") (pintype "passive"))
    )
    (net (code "31") (name "FRAM3") (class "Default")
      (node (ref "IC1") (pin "52") (pinfunction "(RD)PG1_52") (pintype "bidirectional"))
      (node (ref "J$12") (pin "10") (pinfunction "10_10") (pintype "passive"))
    )
    (net (code "32") (name "FRAM4") (class "Default")
      (node (ref "IC1") (pin "51") (pinfunction "(WR)PG0_51") (pintype "bidirectional"))
      (node (ref "J$12") (pin "9") (pinfunction "9_9") (pintype "passive"))
    )
    (net (code "33") (name "FRAM5") (class "Default")
      (node (ref "IC1") (pin "78") (pinfunction "(AD0)PA0_78") (pintype "bidirectional"))
      (node (ref "J$12") (pin "8") (pinfunction "8_8") (pintype "passive"))
    )
    (net (code "34") (name "FRAM6") (class "Default")
      (node (ref "IC1") (pin "77") (pinfunction "(AD1)PA1_77") (pintype "bidirectional"))
      (node (ref "J$12") (pin "7") (pinfunction "7_7") (pintype "passive"))
    )
    (net (code "35") (name "FRAM7") (class "Default")
      (node (ref "IC1") (pin "76") (pinfunction "(AD2)PA2_76") (pintype "bidirectional"))
      (node (ref "J$12") (pin "6") (pinfunction "6_6") (pintype "passive"))
    )
    (net (code "36") (name "FRAM8") (class "Default")
      (node (ref "IC1") (pin "75") (pinfunction "(AD3)PA3_75") (pintype "bidirectional"))
      (node (ref "J$12") (pin "5") (pinfunction "5_5") (pintype "passive"))
    )
    (net (code "37") (name "FRAM9") (class "Default")
      (node (ref "IC1") (pin "74") (pinfunction "(AD4)PA4_74") (pintype "bidirectional"))
      (node (ref "J$12") (pin "4") (pinfunction "4_4") (pintype "passive"))
    )
    (net (code "38") (name "FRAM10") (class "Default")
      (node (ref "IC1") (pin "73") (pinfunction "(AD5)PA5_73") (pintype "bidirectional"))
      (node (ref "J$12") (pin "3") (pinfunction "3_3") (pintype "passive"))
    )
    (net (code "39") (name "FRAM11") (class "Default")
      (node (ref "IC1") (pin "72") (pinfunction "(AD6)PA6_72") (pintype "bidirectional"))
      (node (ref "J$12") (pin "2") (pinfunction "2_2") (pintype "passive"))
    )
    (net (code "40") (name "FRAM12") (class "Default")
      (node (ref "IC1") (pin "71") (pinfunction "(AD7)PA7_71") (pintype "bidirectional"))
      (node (ref "J$12") (pin "1") (pinfunction "1_1") (pintype "passive"))
    )
    (net (code "41") (name "FRAM13") (class "Default")
      (node (ref "IC1") (pin "60") (pinfunction "(A15)PC7_60") (pintype "bidirectional"))
      (node (ref "J$13") (pin "12") (pinfunction "12_12") (pintype "passive"))
    )
    (net (code "42") (name "FRAM14") (class "Default")
      (node (ref "IC1") (pin "59") (pinfunction "(A14)PC6_59") (pintype "bidirectional"))
      (node (ref "J$13") (pin "11") (pinfunction "11_11") (pintype "passive"))
    )
    (net (code "43") (name "FRAM15") (class "Default")
      (node (ref "IC1") (pin "58") (pinfunction "(A13)PC5_58") (pintype "bidirectional"))
      (node (ref "J$13") (pin "10") (pinfunction "10_10") (pintype "passive"))
    )
    (net (code "44") (name "FRAM16") (class "Default")
      (node (ref "IC1") (pin "57") (pinfunction "(A12)PC4_57") (pintype "bidirectional"))
      (node (ref "J$13") (pin "9") (pinfunction "9_9") (pintype "passive"))
    )
    (net (code "45") (name "FRAM17") (class "Default")
      (node (ref "IC1") (pin "56") (pinfunction "(A11)PC3_56") (pintype "bidirectional"))
      (node (ref "J$13") (pin "8") (pinfunction "8_8") (pintype "passive"))
    )
    (net (code "46") (name "FRAM18") (class "Default")
      (node (ref "IC1") (pin "55") (pinfunction "(A10)PC2_55") (pintype "bidirectional"))
      (node (ref "J$13") (pin "7") (pinfunction "7_7") (pintype "passive"))
    )
    (net (code "47") (name "FRAM19") (class "Default")
      (node (ref "IC1") (pin "54") (pinfunction "(A9)PC1_54") (pintype "bidirectional"))
      (node (ref "J$13") (pin "6") (pinfunction "6_6") (pintype "passive"))
    )
    (net (code "48") (name "FRAM20") (class "Default")
      (node (ref "IC1") (pin "53") (pinfunction "(A8)PC0_53") (pintype "bidirectional"))
      (node (ref "J$13") (pin "5") (pinfunction "5_5") (pintype "passive"))
    )
    (net (code "49") (name "FRAM21") (class "Default")
      (node (ref "IC1") (pin "64") (pinfunction "PJ1(TXD3/PCINT10)_64") (pintype "bidirectional"))
      (node (ref "J$13") (pin "4") (pinfunction "4_4") (pintype "passive"))
    )
    (net (code "50") (name "FRAM22") (class "Default")
      (node (ref "IC1") (pin "63") (pinfunction "PJ0(RXD3/PCINT9)_63") (pintype "bidirectional"))
      (node (ref "J$13") (pin "3") (pinfunction "3_3") (pintype "passive"))
    )
    (net (code "51") (name "FRAM23") (class "Default")
      (node (ref "IC1") (pin "26") (pinfunction "(OC0A/OC1C/PCINT7)PB7_26") (pintype "bidirectional"))
      (node (ref "J$14") (pin "3") (pinfunction "3_3") (pintype "passive"))
    )
    (net (code "52") (name "FRAM24") (class "Default")
      (node (ref "IC1") (pin "1") (pinfunction "(OC0B)PG5_1") (pintype "bidirectional"))
      (node (ref "J$14") (pin "2") (pinfunction "2_2") (pintype "passive"))
    )
    (net (code "53") (name "FRAM25") (class "Default")
      (node (ref "IC1") (pin "5") (pinfunction "(OC3A/AIN1)PE3_5") (pintype "bidirectional"))
      (node (ref "J$14") (pin "12") (pinfunction "12_12") (pintype "passive"))
    )
    (net (code "54") (name "FRAM26") (class "Default")
      (node (ref "IC1") (pin "6") (pinfunction "(OC3B/INT4)PE4_6") (pintype "bidirectional"))
      (node (ref "J$14") (pin "11") (pinfunction "11_11") (pintype "passive"))
    )
    (net (code "55") (name "FRAM27") (class "Default")
      (node (ref "IC1") (pin "7") (pinfunction "(OC3C/INT5)PE5_7") (pintype "bidirectional"))
      (node (ref "J$14") (pin "10") (pinfunction "10_10") (pintype "passive"))
    )
    (net (code "56") (name "FRAM28") (class "Default")
      (node (ref "IC1") (pin "12") (pinfunction "PH0(RXD2)_12") (pintype "bidirectional"))
      (node (ref "J$14") (pin "9") (pinfunction "9_9") (pintype "passive"))
    )
    (net (code "57") (name "FRAM29") (class "Default")
      (node (ref "IC1") (pin "13") (pinfunction "PH1(TXD2)_13") (pintype "bidirectional"))
      (node (ref "J$14") (pin "8") (pinfunction "8_8") (pintype "passive"))
    )
    (net (code "58") (name "FRAM30") (class "Default")
      (node (ref "IC1") (pin "15") (pinfunction "PH3(OC4A)_15") (pintype "bidirectional"))
      (node (ref "J$14") (pin "7") (pinfunction "7_7") (pintype "passive"))
    )
    (net (code "59") (name "GND") (class "Default")
      (node (ref "C1") (pin "1") (pinfunction "1_1") (pintype "passive"))
      (node (ref "C10") (pin "1") (pinfunction "1_1") (pintype "passive"))
      (node (ref "C11") (pin "1") (pinfunction "1_1") (pintype "passive"))
      (node (ref "C12") (pin "1") (pinfunction "1_1") (pintype "passive"))
      (node (ref "C14") (pin "1") (pinfunction "1_1") (pintype "passive"))
      (node (ref "C15") (pin "1") (pinfunction "1_1") (pintype "passive"))
      (node (ref "C2") (pin "1") (pinfunction "1_1") (pintype "passive"))
      (node (ref "C3") (pin "1") (pinfunction "1_1") (pintype "passive"))
      (node (ref "C4") (pin "1") (pinfunction "1_1") (pintype "passive"))
      (node (ref "C5") (pin "1") (pinfunction "1_1") (pintype "passive"))
      (node (ref "C6") (pin "1") (pinfunction "1_1") (pintype "passive"))
      (node (ref "C7") (pin "1") (pinfunction "1_1") (pintype "passive"))
      (node (ref "C8") (pin "2") (pinfunction "2_2") (pintype "passive"))
      (node (ref "C9") (pin "2") (pinfunction "2_2") (pintype "passive"))
      (node (ref "CR2") (pin "1") (pinfunction "GROUND_1") (pintype "passive"))
      (node (ref "IC1") (pin "11") (pinfunction "GND_11") (pintype "power_in"))
      (node (ref "IC1") (pin "32") (pinfunction "GND1_32") (pintype "power_in"))
      (node (ref "IC1") (pin "62") (pinfunction "GND2_62") (pintype "power_in"))
      (node (ref "IC1") (pin "81") (pinfunction "GND3_81") (pintype "power_in"))
      (node (ref "IC1") (pin "99") (pinfunction "AGND_99") (pintype "power_in"))
      (node (ref "J$1") (pin "10") (pinfunction "10_10") (pintype "passive"))
      (node (ref "J$1") (pin "11") (pinfunction "11_11") (pintype "passive"))
      (node (ref "J$1") (pin "8") (pinfunction "8_8") (pintype "passive"))
      (node (ref "J$1") (pin "9") (pinfunction "9_9") (pintype "passive"))
      (node (ref "J$11") (pin "3") (pinfunction "3_3") (pintype "passive"))
      (node (ref "J$11") (pin "4") (pinfunction "4_4") (pintype "passive"))
      (node (ref "J$11") (pin "5") (pinfunction "5_5") (pintype "passive"))
      (node (ref "J$2") (pin "11") (pinfunction "11_11") (pintype "passive"))
      (node (ref "J$2") (pin "5") (pinfunction "5_5") (pintype "passive"))
      (node (ref "J$2") (pin "7") (pinfunction "7_7") (pintype "passive"))
      (node (ref "J$2") (pin "9") (pinfunction "9_9") (pintype "passive"))
      (node (ref "J$3") (pin "1") (pinfunction "1_1") (pintype "passive"))
      (node (ref "J$3") (pin "11") (pinfunction "11_11") (pintype "passive"))
      (node (ref "J$3") (pin "3") (pinfunction "3_3") (pintype "passive"))
      (node (ref "J$3") (pin "5") (pinfunction "5_5") (pintype "passive"))
      (node (ref "J$3") (pin "7") (pinfunction "7_7") (pintype "passive"))
      (node (ref "J$3") (pin "9") (pinfunction "9_9") (pintype "passive"))
      (node (ref "J$4") (pin "1") (pinfunction "1_1") (pintype "passive"))
      (node (ref "J$4") (pin "11") (pinfunction "11_11") (pintype "passive"))
      (node (ref "J$4") (pin "3") (pinfunction "3_3") (pintype "passive"))
      (node (ref "J$4") (pin "5") (pinfunction "5_5") (pintype "passive"))
      (node (ref "J$4") (pin "7") (pinfunction "7_7") (pintype "passive"))
      (node (ref "J$4") (pin "9") (pinfunction "9_9") (pintype "passive"))
      (node (ref "R13") (pin "1") (pinfunction "11_1") (pintype "passive"))
      (node (ref "U1") (pin "GND") (pinfunction "GND_GND") (pintype "bidirectional"))
      (node (ref "U2") (pin "4") (pinfunction "GND_4") (pintype "passive"))
      (node (ref "U3") (pin "3") (pinfunction "GND_3") (pintype "power_in"))
      (node (ref "U3") (pin "33") (pinfunction "EPAD_33") (pintype "passive"))
      (node (ref "U4") (pin "12") (pinfunction "GND_12") (pintype "power_in"))
      (node (ref "U4") (pin "15") (pinfunction "~{E}_15") (pintype "passive"))
      (node (ref "U5") (pin "12") (pinfunction "GND_12") (pintype "power_in"))
      (node (ref "U6") (pin "4") (pinfunction "GND_4") (pintype "passive"))
      (node (ref "U7") (pin "4") (pinfunction "GND_4") (pintype "passive"))
      (node (ref "U8") (pin "4") (pinfunction "GND_4") (pintype "passive"))
    )
    (net (code "60") (name "M8RXD") (class "Default")
      (node (ref "R12") (pin "1") (pinfunction "11_1") (pintype "passive"))
      (node (ref "U3") (pin "8") (pinfunction "PD3_8") (pintype "bidirectional"))
    )
    (net (code "61") (name "M8TXD") (class "Default")
      (node (ref "R11") (pin "1") (pinfunction "11_1") (pintype "passive"))
      (node (ref "U3") (pin "9") (pinfunction "PD2_9") (pintype "bidirectional"))
    )
    (net (code "62") (name "MISO") (class "Default")
      (node (ref "IC1") (pin "22") (pinfunction "(MISO/PCINT3)PB3_22") (pintype "bidirectional"))
      (node (ref "J$7") (pin "12") (pinfunction "12_12") (pintype "passive"))
      (node (ref "J$7") (pin "3") (pinfunction "3_3") (pintype "passive"))
      (node (ref "J$7") (pin "6") (pinfunction "6_6") (pintype "passive"))
      (node (ref "J$7") (pin "9") (pinfunction "9_9") (pintype "passive"))
      (node (ref "J$8") (pin "12") (pinfunction "12_12") (pintype "passive"))
      (node (ref "J$8") (pin "3") (pinfunction "3_3") (pintype "passive"))
      (node (ref "J$8") (pin "6") (pinfunction "6_6") (pintype "passive"))
      (node (ref "J$8") (pin "9") (pinfunction "9_9") (pintype "passive"))
    )
    (net (code "63") (name "MISO2") (class "Default")
      (node (ref "J2") (pin "2") (pinfunction "2_2") (pintype "passive"))
      (node (ref "U3") (pin "17") (pinfunction "PB3_17") (pintype "bidirectional"))
    )
    (net (code "64") (name "MOSI") (class "Default")
      (node (ref "IC1") (pin "21") (pinfunction "(MOSI/PCINT2)PB2_21") (pintype "bidirectional"))
      (node (ref "J$7") (pin "11") (pinfunction "11_11") (pintype "passive"))
      (node (ref "J$7") (pin "2") (pinfunction "2_2") (pintype "passive"))
      (node (ref "J$7") (pin "5") (pinfunction "5_5") (pintype "passive"))
      (node (ref "J$7") (pin "8") (pinfunction "8_8") (pintype "passive"))
      (node (ref "J$8") (pin "11") (pinfunction "11_11") (pintype "passive"))
      (node (ref "J$8") (pin "2") (pinfunction "2_2") (pintype "passive"))
      (node (ref "J$8") (pin "5") (pinfunction "5_5") (pintype "passive"))
      (node (ref "J$8") (pin "8") (pinfunction "8_8") (pintype "passive"))
    )
    (net (code "65") (name "MOSI2") (class "Default")
      (node (ref "J2") (pin "3") (pinfunction "3_3") (pintype "passive"))
      (node (ref "U3") (pin "16") (pinfunction "PB2_16") (pintype "bidirectional"))
    )
    (net (code "66") (name "Net-(R15-22)") (class "Default")
      (node (ref "R15") (pin "2") (pinfunction "22_2") (pintype "passive"))
      (node (ref "SJ2") (pin "2") (pinfunction "2_2") (pintype "passive"))
    )
    (net (code "67") (name "Net-(R16-22)") (class "Default")
      (node (ref "R16") (pin "2") (pinfunction "22_2") (pintype "passive"))
      (node (ref "SJ3") (pin "2") (pinfunction "2_2") (pintype "passive"))
    )
    (net (code "68") (name "PD4") (class "Default")
      (node (ref "IC1") (pin "47") (pinfunction "(ICP1)PD4_47") (pintype "bidirectional"))
    )
    (net (code "69") (name "PD5") (class "Default")
      (node (ref "IC1") (pin "48") (pinfunction "(XCK1)PD5_48") (pintype "bidirectional"))
    )
    (net (code "70") (name "PD6") (class "Default")
      (node (ref "IC1") (pin "49") (pinfunction "(T1)PD6_49") (pintype "bidirectional"))
    )
    (net (code "71") (name "PE0") (class "Default")
      (node (ref "IC1") (pin "2") (pinfunction "(RXD0/PCIN8)PE0_2") (pintype "bidirectional"))
      (node (ref "Q2") (pin "D") (pinfunction "D_D") (pintype "passive"))
      (node (ref "R12") (pin "2") (pinfunction "22_2") (pintype "passive"))
      (node (ref "R4") (pin "2") (pinfunction "22_2") (pintype "passive"))
    )
    (net (code "72") (name "PE0_3.3V") (class "Default")
      (node (ref "Q2") (pin "S") (pinfunction "S_S") (pintype "passive"))
      (node (ref "R2") (pin "2") (pinfunction "22_2") (pintype "passive"))
      (node (ref "U2") (pin "3") (pinfunction "DI_3") (pintype "passive"))
    )
    (net (code "73") (name "PE1") (class "Default")
      (node (ref "IC1") (pin "3") (pinfunction "(TXD0)PE1_3") (pintype "bidirectional"))
      (node (ref "Q1") (pin "D") (pinfunction "D_D") (pintype "passive"))
      (node (ref "R11") (pin "2") (pinfunction "22_2") (pintype "passive"))
      (node (ref "R3") (pin "2") (pinfunction "22_2") (pintype "passive"))
    )
    (net (code "74") (name "PE1_3.3V") (class "Default")
      (node (ref "Q1") (pin "S") (pinfunction "S_S") (pintype "passive"))
      (node (ref "R1") (pin "2") (pinfunction "22_2") (pintype "passive"))
      (node (ref "U2") (pin "2") (pinfunction "RO_2") (pintype "passive"))
    )
    (net (code "75") (name "PE2") (class "Default")
      (node (ref "IC1") (pin "4") (pinfunction "(XCK0/AIN0)PE2_4") (pintype "bidirectional"))
    )
    (net (code "76") (name "PE6") (class "Default")
      (node (ref "IC1") (pin "8") (pinfunction "(T3/INT6)PE6_8") (pintype "bidirectional"))
    )
    (net (code "77") (name "PE7") (class "Default")
      (node (ref "IC1") (pin "9") (pinfunction "(CLKO/ICP3/INT7)PE7_9") (pintype "bidirectional"))
    )
    (net (code "78") (name "PG3") (class "Default")
      (node (ref "IC1") (pin "28") (pinfunction "(TOSC2)PG3_28") (pintype "bidirectional"))
    )
    (net (code "79") (name "PG4") (class "Default")
      (node (ref "IC1") (pin "29") (pinfunction "(TOSC1)PG4_29") (pintype "bidirectional"))
    )
    (net (code "80") (name "PH2") (class "Default")
      (node (ref "IC1") (pin "14") (pinfunction "PH2(XCK2)_14") (pintype "bidirectional"))
    )
    (net (code "81") (name "PH7") (class "Default")
      (node (ref "IC1") (pin "27") (pinfunction "PH7(T4)_27") (pintype "bidirectional"))
    )
    (net (code "82") (name "PJ2") (class "Default")
      (node (ref "IC1") (pin "65") (pinfunction "PJ2(XCK3/PCINT11)_65") (pintype "bidirectional"))
    )
    (net (code "83") (name "PJ3") (class "Default")
      (node (ref "IC1") (pin "66") (pinfunction "PJ3(PCINT12)_66") (pintype "bidirectional"))
    )
    (net (code "84") (name "PJ4") (class "Default")
      (node (ref "IC1") (pin "67") (pinfunction "PJ4(PCINT13)_67") (pintype "bidirectional"))
    )
    (net (code "85") (name "PJ5") (class "Default")
      (node (ref "IC1") (pin "68") (pinfunction "PJ5(PCINT14)_68") (pintype "bidirectional"))
    )
    (net (code "86") (name "PJ6") (class "Default")
      (node (ref "IC1") (pin "69") (pinfunction "PJ6(PCINT15)_69") (pintype "bidirectional"))
    )
    (net (code "87") (name "PJ7") (class "Default")
      (node (ref "IC1") (pin "79") (pinfunction "PJ7_79") (pintype "bidirectional"))
    )
    (net (code "88") (name "PK3") (class "Default")
      (node (ref "IC1") (pin "86") (pinfunction "PK3(ADC11/PCINT19)_86") (pintype "bidirectional"))
      (node (ref "U4") (pin "1") (pinfunction "COMMON_IN/OUT_1") (pintype "passive"))
    )
    (net (code "89") (name "PK4") (class "Default")
      (node (ref "IC1") (pin "85") (pinfunction "PK4(ADC12/PCINT20)_85") (pintype "bidirectional"))
      (node (ref "U4") (pin "10") (pinfunction "S0_10") (pintype "passive"))
    )
    (net (code "90") (name "PK5") (class "Default")
      (node (ref "IC1") (pin "84") (pinfunction "PK5(ADC13/PCINT21)_84") (pintype "bidirectional"))
      (node (ref "U4") (pin "11") (pinfunction "S1_11") (pintype "passive"))
    )
    (net (code "91") (name "PK6") (class "Default")
      (node (ref "IC1") (pin "83") (pinfunction "PK6(ADC14/PCINT22)_83") (pintype "bidirectional"))
      (node (ref "U4") (pin "14") (pinfunction "S2_14") (pintype "passive"))
    )
    (net (code "92") (name "PK7") (class "Default")
      (node (ref "IC1") (pin "82") (pinfunction "PK7(ADC15/PCINT23)_82") (pintype "bidirectional"))
      (node (ref "U4") (pin "13") (pinfunction "S3_13") (pintype "passive"))
    )
    (net (code "93") (name "RESET") (class "Default")
      (node (ref "C13") (pin "2") (pinfunction "2_2") (pintype "passive"))
      (node (ref "C7") (pin "2") (pinfunction "2_2") (pintype "passive"))
      (node (ref "CR3") (pin "2") (pinfunction "21_2") (pintype "passive"))
      (node (ref "IC1") (pin "30") (pinfunction "RESET_30") (pintype "input"))
      (node (ref "J$14") (pin "1") (pinfunction "1_1") (pintype "passive"))
      (node (ref "R5") (pin "2") (pinfunction "22_2") (pintype "passive"))
      (node (ref "SJ1") (pin "1") (pinfunction "1_1") (pintype "passive"))
      (node (ref "SJ1") (pin "2") (pinfunction "2_2") (pintype "passive"))
    )
    (net (code "94") (name "RESET2") (class "Default")
      (node (ref "CR4") (pin "2") (pinfunction "21_2") (pintype "passive"))
      (node (ref "J2") (pin "1") (pinfunction "1_1") (pintype "passive"))
      (node (ref "R10") (pin "2") (pinfunction "22_2") (pintype "passive"))
      (node (ref "U3") (pin "24") (pinfunction "~{RESET}_24") (pintype "input"))
    )
    (net (code "95") (name "RESET_TCA") (class "Default")
      (node (ref "R14") (pin "2") (pinfunction "22_2") (pintype "passive"))
      (node (ref "U5") (pin "3") (pinfunction "~{RESET}_3") (pintype "input"))
    )
    (net (code "96") (name "RX+") (class "Default")
      (node (ref "J$1") (pin "4") (pinfunction "4_4") (pintype "passive"))
      (node (ref "U2") (pin "8") (pinfunction "A_8") (pintype "passive"))
    )
    (net (code "97") (name "RX-") (class "Default")
      (node (ref "J$1") (pin "3") (pinfunction "3_3") (pintype "passive"))
      (node (ref "U2") (pin "7") (pinfunction "B_7") (pintype "passive"))
    )
    (net (code "98") (name "RX1") (class "Default")
      (node (ref "IC1") (pin "45") (pinfunction "(RXD1/INT2)PD2_45") (pintype "bidirectional"))
      (node (ref "J$13") (pin "1") (pinfunction "1_1") (pintype "passive"))
    )
    (net (code "99") (name "RXL") (class "Default")
      (node (ref "U3") (pin "10") (pinfunction "PD4_10") (pintype "bidirectional"))
    )
    (net (code "100") (name "SCK") (class "Default")
      (node (ref "IC1") (pin "20") (pinfunction "(SCK/PCINT1)PB1_20") (pintype "bidirectional"))
      (node (ref "J$7") (pin "1") (pinfunction "1_1") (pintype "passive"))
      (node (ref "J$7") (pin "10") (pinfunction "10_10") (pintype "passive"))
      (node (ref "J$7") (pin "4") (pinfunction "4_4") (pintype "passive"))
      (node (ref "J$7") (pin "7") (pinfunction "7_7") (pintype "passive"))
      (node (ref "J$8") (pin "1") (pinfunction "1_1") (pintype "passive"))
      (node (ref "J$8") (pin "10") (pinfunction "10_10") (pintype "passive"))
      (node (ref "J$8") (pin "4") (pinfunction "4_4") (pintype "passive"))
      (node (ref "J$8") (pin "7") (pinfunction "7_7") (pintype "passive"))
    )
    (net (code "101") (name "SCK2") (class "Default")
      (node (ref "J2") (pin "4") (pinfunction "4_4") (pintype "passive"))
      (node (ref "U3") (pin "15") (pinfunction "PB1_15") (pintype "bidirectional"))
    )
    (net (code "102") (name "SCL") (class "Default")
      (node (ref "IC1") (pin "43") (pinfunction "(SCL/INT0)PD0_43") (pintype "bidirectional"))
      (node (ref "J$5") (pin "10") (pinfunction "10_10") (pintype "passive"))
      (node (ref "J$5") (pin "12") (pinfunction "12_12") (pintype "passive"))
      (node (ref "J$5") (pin "2") (pinfunction "2_2") (pintype "passive"))
      (node (ref "J$5") (pin "4") (pinfunction "4_4") (pintype "passive"))
      (node (ref "J$5") (pin "6") (pinfunction "6_6") (pintype "passive"))
      (node (ref "J$5") (pin "8") (pinfunction "8_8") (pintype "passive"))
      (node (ref "J$6") (pin "10") (pinfunction "10_10") (pintype "passive"))
      (node (ref "J$6") (pin "12") (pinfunction "12_12") (pintype "passive"))
      (node (ref "J$6") (pin "8") (pinfunction "8_8") (pintype "passive"))
      (node (ref "R6") (pin "2") (pinfunction "22_2") (pintype "passive"))
      (node (ref "SJ3") (pin "1") (pinfunction "1_1") (pintype "passive"))
      (node (ref "U5") (pin "22") (pinfunction "SCL_22") (pintype "passive"))
    )
    (net (code "103") (name "SDA") (class "Default")
      (node (ref "IC1") (pin "44") (pinfunction "(SDA/INT1)PD1_44") (pintype "bidirectional"))
      (node (ref "J$5") (pin "1") (pinfunction "1_1") (pintype "passive"))
      (node (ref "J$5") (pin "11") (pinfunction "11_11") (pintype "passive"))
      (node (ref "J$5") (pin "3") (pinfunction "3_3") (pintype "passive"))
      (node (ref "J$5") (pin "5") (pinfunction "5_5") (pintype "passive"))
      (node (ref "J$5") (pin "7") (pinfunction "7_7") (pintype "passive"))
      (node (ref "J$5") (pin "9") (pinfunction "9_9") (pintype "passive"))
      (node (ref "J$6") (pin "11") (pinfunction "11_11") (pintype "passive"))
      (node (ref "J$6") (pin "7") (pinfunction "7_7") (pintype "passive"))
      (node (ref "J$6") (pin "9") (pinfunction "9_9") (pintype "passive"))
      (node (ref "R7") (pin "2") (pinfunction "22_2") (pintype "passive"))
      (node (ref "SJ2") (pin "1") (pinfunction "1_1") (pintype "passive"))
      (node (ref "U5") (pin "23") (pinfunction "SDA_23") (pintype "passive"))
    )
    (net (code "104") (name "TEC1_ENABLE") (class "Default")
      (node (ref "IC1") (pin "40") (pinfunction "PL5(OC5C)_40") (pintype "bidirectional"))
      (node (ref "J$15") (pin "9") (pinfunction "9_9") (pintype "passive"))
    )
    (net (code "105") (name "TEC1_INPUT1") (class "Default")
      (node (ref "IC1") (pin "50") (pinfunction "(T0)PD7_50") (pintype "bidirectional"))
      (node (ref "J$15") (pin "12") (pinfunction "12_12") (pintype "passive"))
    )
    (net (code "106") (name "TEC1_INPUT2") (class "Default")
      (node (ref "IC1") (pin "42") (pinfunction "PL7_42") (pintype "bidirectional"))
      (node (ref "J$15") (pin "11") (pinfunction "11_11") (pintype "passive"))
    )
    (net (code "107") (name "TEC2_ENABLE") (class "Default")
      (node (ref "IC1") (pin "39") (pinfunction "PL4(OC5B)_39") (pintype "bidirectional"))
      (node (ref "J$15") (pin "8") (pinfunction "8_8") (pintype "passive"))
    )
    (net (code "108") (name "TEC2_INPUT1") (class "Default")
      (node (ref "IC1") (pin "41") (pinfunction "PL6_41") (pintype "bidirectional"))
      (node (ref "J$15") (pin "10") (pinfunction "10_10") (pintype "passive"))
    )
    (net (code "109") (name "TEC2_INPUT2") (class "Default")
      (node (ref "IC1") (pin "37") (pinfunction "PL2(T5)_37") (pintype "bidirectional"))
      (node (ref "J$15") (pin "6") (pinfunction "6_6") (pintype "passive"))
    )
    (net (code "110") (name "TEC3_ENABLE") (class "Default")
      (node (ref "IC1") (pin "38") (pinfunction "PL3(OC5A)_38") (pintype "bidirectional"))
      (node (ref "J$15") (pin "7") (pinfunction "7_7") (pintype "passive"))
    )
    (net (code "111") (name "TEC3_INPUT1") (class "Default")
      (node (ref "IC1") (pin "36") (pinfunction "PL1(ICP5)_36") (pintype "bidirectional"))
      (node (ref "J$15") (pin "5") (pinfunction "5_5") (pintype "passive"))
    )
    (net (code "112") (name "TEC3_INPUT2") (class "Default")
      (node (ref "IC1") (pin "35") (pinfunction "PL0(ICP4)_35") (pintype "bidirectional"))
      (node (ref "J$15") (pin "4") (pinfunction "4_4") (pintype "passive"))
    )
    (net (code "113") (name "TEMP") (class "Default")
      (node (ref "IC1") (pin "18") (pinfunction "PH6(OC2B)_18") (pintype "bidirectional"))
      (node (ref "J$1") (pin "5") (pinfunction "5_5") (pintype "passive"))
      (node (ref "J$1") (pin "6") (pinfunction "6_6") (pintype "passive"))
      (node (ref "J$1") (pin "7") (pinfunction "7_7") (pintype "passive"))
      (node (ref "J$15") (pin "3") (pinfunction "3_3") (pintype "passive"))
      (node (ref "R17") (pin "1") (pinfunction "11_1") (pintype "passive"))
      (node (ref "U6") (pin "1") (pinfunction "DQ_1") (pintype "bidirectional"))
      (node (ref "U7") (pin "1") (pinfunction "DQ_1") (pintype "bidirectional"))
      (node (ref "U8") (pin "1") (pinfunction "DQ_1") (pintype "bidirectional"))
    )
    (net (code "114") (name "THERMISTOR1") (class "Default")
      (node (ref "IC1") (pin "97") (pinfunction "(ADC0)PF0_97") (pintype "bidirectional"))
      (node (ref "J$9") (pin "12") (pinfunction "12_12") (pintype "passive"))
    )
    (net (code "115") (name "THERMISTOR2") (class "Default")
      (node (ref "IC1") (pin "96") (pinfunction "(ADC1)PF1_96") (pintype "bidirectional"))
      (node (ref "J$9") (pin "11") (pinfunction "11_11") (pintype "passive"))
    )
    (net (code "116") (name "THERMISTOR3") (class "Default")
      (node (ref "IC1") (pin "95") (pinfunction "(ADC2)PF2_95") (pintype "bidirectional"))
      (node (ref "J$9") (pin "10") (pinfunction "10_10") (pintype "passive"))
    )
    (net (code "117") (name "THERMISTOR4") (class "Default")
      (node (ref "IC1") (pin "94") (pinfunction "(ADC3)PF3_94") (pintype "bidirectional"))
      (node (ref "J$9") (pin "9") (pinfunction "9_9") (pintype "passive"))
    )
    (net (code "118") (name "THERMISTOR5") (class "Default")
      (node (ref "IC1") (pin "93") (pinfunction "(ADC4/TCK)PF4_93") (pintype "bidirectional"))
      (node (ref "J$9") (pin "8") (pinfunction "8_8") (pintype "passive"))
    )
    (net (code "119") (name "THERMISTOR6") (class "Default")
      (node (ref "IC1") (pin "92") (pinfunction "(ADC5/TMS)PF5_92") (pintype "bidirectional"))
      (node (ref "J$9") (pin "7") (pinfunction "7_7") (pintype "passive"))
    )
    (net (code "120") (name "THERMISTOR7") (class "Default")
      (node (ref "IC1") (pin "91") (pinfunction "(ADC6/TDO)PF6_91") (pintype "bidirectional"))
      (node (ref "J$9") (pin "6") (pinfunction "6_6") (pintype "passive"))
    )
    (net (code "121") (name "THERMISTOR8") (class "Default")
      (node (ref "IC1") (pin "90") (pinfunction "(ADC7/TDI)PF7_90") (pintype "bidirectional"))
      (node (ref "J$9") (pin "5") (pinfunction "5_5") (pintype "passive"))
    )
    (net (code "122") (name "THERMISTOR9") (class "Default")
      (node (ref "IC1") (pin "89") (pinfunction "PK0(ADC8/PCINT16)_89") (pintype "bidirectional"))
      (node (ref "J$9") (pin "4") (pinfunction "4_4") (pintype "passive"))
    )
    (net (code "123") (name "THERMISTOR10") (class "Default")
      (node (ref "IC1") (pin "88") (pinfunction "PK1(ADC9/PCINT17)_88") (pintype "bidirectional"))
      (node (ref "J$9") (pin "3") (pinfunction "3_3") (pintype "passive"))
    )
    (net (code "124") (name "THERMISTOR11") (class "Default")
      (node (ref "IC1") (pin "87") (pinfunction "PK2(ADC10/PCINT18)_87") (pintype "bidirectional"))
      (node (ref "J$9") (pin "2") (pinfunction "2_2") (pintype "passive"))
    )
    (net (code "125") (name "THERMISTOR12") (class "Default")
      (node (ref "J$10") (pin "7") (pinfunction "7_7") (pintype "passive"))
      (node (ref "U4") (pin "8") (pinfunction "I1_8") (pintype "passive"))
    )
    (net (code "126") (name "THERMISTOR13") (class "Default")
      (node (ref "J$10") (pin "8") (pinfunction "8_8") (pintype "passive"))
      (node (ref "U4") (pin "7") (pinfunction "I2_7") (pintype "passive"))
    )
    (net (code "127") (name "THERMISTOR14") (class "Default")
      (node (ref "J$10") (pin "9") (pinfunction "9_9") (pintype "passive"))
      (node (ref "U4") (pin "6") (pinfunction "I3_6") (pintype "passive"))
    )
    (net (code "128") (name "THERMISTOR15") (class "Default")
      (node (ref "J$10") (pin "10") (pinfunction "10_10") (pintype "passive"))
      (node (ref "U4") (pin "5") (pinfunction "I4_5") (pintype "passive"))
    )
    (net (code "129") (name "THERMISTOR16") (class "Default")
      (node (ref "J$10") (pin "11") (pinfunction "11_11") (pintype "passive"))
      (node (ref "U4") (pin "4") (pinfunction "I5_4") (pintype "passive"))
    )
    (net (code "130") (name "THERMISTOR17") (class "Default")
      (node (ref "J$10") (pin "12") (pinfunction "12_12") (pintype "passive"))
      (node (ref "U4") (pin "3") (pinfunction "I6_3") (pintype "passive"))
    )
    (net (code "131") (name "THERMISTOR18") (class "Default")
      (node (ref "J$9") (pin "1") (pinfunction "1_1") (pintype "passive"))
      (node (ref "U4") (pin "2") (pinfunction "I7_2") (pintype "passive"))
    )
    (net (code "132") (name "THERMISTOR19") (class "Default")
      (node (ref "J$10") (pin "6") (pinfunction "6_6") (pintype "passive"))
      (node (ref "U4") (pin "23") (pinfunction "I8_23") (pintype "passive"))
    )
    (net (code "133") (name "THERMISTOR20") (class "Default")
      (node (ref "J$10") (pin "5") (pinfunction "5_5") (pintype "passive"))
      (node (ref "U4") (pin "22") (pinfunction "I9_22") (pintype "passive"))
    )
    (net (code "134") (name "THERMISTOR21") (class "Default")
      (node (ref "J$10") (pin "4") (pinfunction "4_4") (pintype "passive"))
      (node (ref "U4") (pin "21") (pinfunction "I10_21") (pintype "passive"))
    )
    (net (code "135") (name "THERMISTOR22") (class "Default")
      (node (ref "J$10") (pin "3") (pinfunction "3_3") (pintype "passive"))
      (node (ref "U4") (pin "20") (pinfunction "I11_20") (pintype "passive"))
    )
    (net (code "136") (name "THERMISTOR23") (class "Default")
      (node (ref "J$10") (pin "2") (pinfunction "2_2") (pintype "passive"))
      (node (ref "U4") (pin "19") (pinfunction "I12_19") (pintype "passive"))
    )
    (net (code "137") (name "THERMISTOR24") (class "Default")
      (node (ref "J$10") (pin "1") (pinfunction "1_1") (pintype "passive"))
      (node (ref "U4") (pin "18") (pinfunction "I13_18") (pintype "passive"))
    )
    (net (code "138") (name "THERMISTOR25") (class "Default")
      (node (ref "J$11") (pin "11") (pinfunction "11_11") (pintype "passive"))
      (node (ref "U4") (pin "17") (pinfunction "I14_17") (pintype "passive"))
    )
    (net (code "139") (name "THERMISTOR26") (class "Default")
      (node (ref "J$11") (pin "12") (pinfunction "12_12") (pintype "passive"))
      (node (ref "U4") (pin "16") (pinfunction "I15_16") (pintype "passive"))
    )
    (net (code "140") (name "THERMISTOR27") (class "Default")
      (node (ref "J$11") (pin "10") (pinfunction "10_10") (pintype "passive"))
      (node (ref "U4") (pin "9") (pinfunction "I0_9") (pintype "passive"))
    )
    (net (code "141") (name "TX+") (class "Default")
      (node (ref "J$1") (pin "2") (pinfunction "2_2") (pintype "passive"))
      (node (ref "U2") (pin "6") (pinfunction "Z_6") (pintype "passive"))
    )
    (net (code "142") (name "TX-") (class "Default")
      (node (ref "J$1") (pin "1") (pinfunction "1_1") (pintype "passive"))
      (node (ref "U2") (pin "5") (pinfunction "Y_5") (pintype "passive"))
    )
    (net (code "143") (name "TX1") (class "Default")
      (node (ref "IC1") (pin "46") (pinfunction "(TXD1/INT3)PD3_46") (pintype "bidirectional"))
      (node (ref "J$13") (pin "2") (pinfunction "2_2") (pintype "passive"))
    )
    (net (code "144") (name "TXL") (class "Default")
      (node (ref "U3") (pin "11") (pinfunction "PD5_11") (pintype "bidirectional"))
    )
    (net (code "145") (name "UGND") (class "Default")
      (node (ref "U3") (pin "28") (pinfunction "UGND_28") (pintype "power_in"))
    )
    (net (code "146") (name "UVCC") (class "Default")
      (node (ref "U3") (pin "31") (pinfunction "UVCC_31") (pintype "power_in"))
    )
    (net (code "147") (name "VIN") (class "Default")
      (node (ref "C1") (pin "2") (pinfunction "2_2") (pintype "passive"))
      (node (ref "CR1") (pin "1") (pinfunction "12_1") (pintype "passive"))
      (node (ref "CR2") (pin "3") (pinfunction "INPUT_3") (pintype "passive"))
      (node (ref "J$1") (pin "12") (pinfunction "12_12") (pintype "passive"))
      (node (ref "J$2") (pin "10") (pinfunction "10_10") (pintype "passive"))
      (node (ref "J$2") (pin "12") (pinfunction "12_12") (pintype "passive"))
      (node (ref "J$2") (pin "6") (pinfunction "6_6") (pintype "passive"))
      (node (ref "J$2") (pin "8") (pinfunction "8_8") (pintype "passive"))
    )
    (net (code "148") (name "XT1") (class "Default")
      (node (ref "C11") (pin "2") (pinfunction "2_2") (pintype "passive"))
      (node (ref "Q4") (pin "1") (pinfunction "1_1") (pintype "bidirectional"))
      (node (ref "R9") (pin "2") (pinfunction "22_2") (pintype "passive"))
      (node (ref "U3") (pin "1") (pinfunction "XTAL1_1") (pintype "input"))
    )
    (net (code "149") (name "XT2") (class "Default")
      (node (ref "C10") (pin "2") (pinfunction "2_2") (pintype "passive"))
      (node (ref "Q4") (pin "2") (pinfunction "2_2") (pintype "bidirectional"))
      (node (ref "R9") (pin "1") (pinfunction "11_1") (pintype "passive"))
      (node (ref "U3") (pin "2") (pinfunction "XTAL2_2") (pintype "output"))
    )
    (net (code "150") (name "XTAL1") (class "Default")
      (node (ref "C9") (pin "1") (pinfunction "1_1") (pintype "passive"))
      (node (ref "IC1") (pin "34") (pinfunction "XTAL1_34") (pintype "input"))
      (node (ref "Q3") (pin "1") (pinfunction "1_1") (pintype "bidirectional"))
      (node (ref "R8") (pin "2") (pinfunction "22_2") (pintype "passive"))
    )
    (net (code "151") (name "XTAL2") (class "Default")
      (node (ref "C8") (pin "1") (pinfunction "1_1") (pintype "passive"))
      (node (ref "IC1") (pin "33") (pinfunction "XTAL2_33") (pintype "output"))
      (node (ref "Q3") (pin "2") (pinfunction "2_2") (pintype "bidirectional"))
      (node (ref "R8") (pin "1") (pinfunction "11_1") (pintype "passive"))
    )
    (net (code "152") (name "unconnected-(CR1-21-Pad2)") (class "Default")
      (node (ref "CR1") (pin "2") (pinfunction "21_2") (pintype "passive"))
    )
    (net (code "153") (name "unconnected-(H1-MOUNT-PadB3,2)") (class "Default")
      (node (ref "H1") (pin "B3,2") (pinfunction "MOUNT_B3,2") (pintype "passive"))
    )
    (net (code "154") (name "unconnected-(H2-MOUNT-PadB3,2)") (class "Default")
      (node (ref "H2") (pin "B3,2") (pinfunction "MOUNT_B3,2") (pintype "passive"))
    )
    (net (code "155") (name "unconnected-(H3-MOUNT-PadB3,2)") (class "Default")
      (node (ref "H3") (pin "B3,2") (pinfunction "MOUNT_B3,2") (pintype "passive"))
    )
    (net (code "156") (name "unconnected-(H4-MOUNT-PadB3,2)") (class "Default")
      (node (ref "H4") (pin "B3,2") (pinfunction "MOUNT_B3,2") (pintype "passive"))
    )
    (net (code "157") (name "unconnected-(J$2-Pad1)") (class "Default")
      (node (ref "J$2") (pin "1") (pinfunction "1_1") (pintype "passive"))
    )
    (net (code "158") (name "unconnected-(J$2-Pad2)") (class "Default")
      (node (ref "J$2") (pin "2") (pinfunction "2_2") (pintype "passive"))
    )
    (net (code "159") (name "unconnected-(J$2-Pad3)") (class "Default")
      (node (ref "J$2") (pin "3") (pinfunction "3_3") (pintype "passive"))
    )
    (net (code "160") (name "unconnected-(J$2-Pad4)") (class "Default")
      (node (ref "J$2") (pin "4") (pinfunction "4_4") (pintype "passive"))
    )
    (net (code "161") (name "unconnected-(J$11-Pad1)") (class "Default")
      (node (ref "J$11") (pin "1") (pinfunction "1_1") (pintype "passive"))
    )
    (net (code "162") (name "unconnected-(J$11-Pad2)") (class "Default")
      (node (ref "J$11") (pin "2") (pinfunction "2_2") (pintype "passive"))
    )
    (net (code "163") (name "unconnected-(U1-P4-PadNC{slash}ADJ)") (class "Default")
      (node (ref "U1") (pin "NC/ADJ") (pinfunction "P4_NC/ADJ") (pintype "bidirectional"))
    )
    (net (code "164") (name "unconnected-(U3-D+-Pad29)") (class "Default")
      (node (ref "U3") (pin "29") (pinfunction "D+_29") (pintype "passive"))
    )
    (net (code "165") (name "unconnected-(U3-D--Pad30)") (class "Default")
      (node (ref "U3") (pin "30") (pinfunction "D-_30") (pintype "passive"))
    )
    (net (code "166") (name "unconnected-(U3-PB0-Pad14)") (class "Default")
      (node (ref "U3") (pin "14") (pinfunction "PB0_14") (pintype "bidirectional"))
    )
    (net (code "167") (name "unconnected-(U3-PB4-Pad18)") (class "Default")
      (node (ref "U3") (pin "18") (pinfunction "PB4_18") (pintype "bidirectional"))
    )
    (net (code "168") (name "unconnected-(U3-PB5-Pad19)") (class "Default")
      (node (ref "U3") (pin "19") (pinfunction "PB5_19") (pintype "bidirectional"))
    )
    (net (code "169") (name "unconnected-(U3-PB6-Pad20)") (class "Default")
      (node (ref "U3") (pin "20") (pinfunction "PB6_20") (pintype "bidirectional"))
    )
    (net (code "170") (name "unconnected-(U3-PB7-Pad21)") (class "Default")
      (node (ref "U3") (pin "21") (pinfunction "PB7_21") (pintype "bidirectional"))
    )
    (net (code "171") (name "unconnected-(U3-PC2-Pad5)") (class "Default")
      (node (ref "U3") (pin "5") (pinfunction "PC2_5") (pintype "bidirectional"))
    )
    (net (code "172") (name "unconnected-(U3-PC4-Pad26)") (class "Default")
      (node (ref "U3") (pin "26") (pinfunction "PC4_26") (pintype "bidirectional"))
    )
    (net (code "173") (name "unconnected-(U3-PC5-Pad25)") (class "Default")
      (node (ref "U3") (pin "25") (pinfunction "PC5_25") (pintype "bidirectional"))
    )
    (net (code "174") (name "unconnected-(U3-PC6-Pad22)") (class "Default")
      (node (ref "U3") (pin "22") (pinfunction "PC6_22") (pintype "bidirectional"))
    )
    (net (code "175") (name "unconnected-(U3-PC7-Pad23)") (class "Default")
      (node (ref "U3") (pin "23") (pinfunction "PC7_23") (pintype "bidirectional"))
    )
    (net (code "176") (name "unconnected-(U3-PD0-Pad6)") (class "Default")
      (node (ref "U3") (pin "6") (pinfunction "PD0_6") (pintype "bidirectional"))
    )
    (net (code "177") (name "unconnected-(U3-PD1-Pad7)") (class "Default")
      (node (ref "U3") (pin "7") (pinfunction "PD1_7") (pintype "bidirectional"))
    )
    (net (code "178") (name "unconnected-(U3-PD6-Pad12)") (class "Default")
      (node (ref "U3") (pin "12") (pinfunction "PD6_12") (pintype "bidirectional"))
    )
    (net (code "179") (name "unconnected-(U3-UCAP-Pad27)") (class "Default")
      (node (ref "U3") (pin "27") (pinfunction "UCAP_27") (pintype "passive"))
    )
  )
)
